# AD.net
KiCad netlist of a schematic drawn in Altium Designer
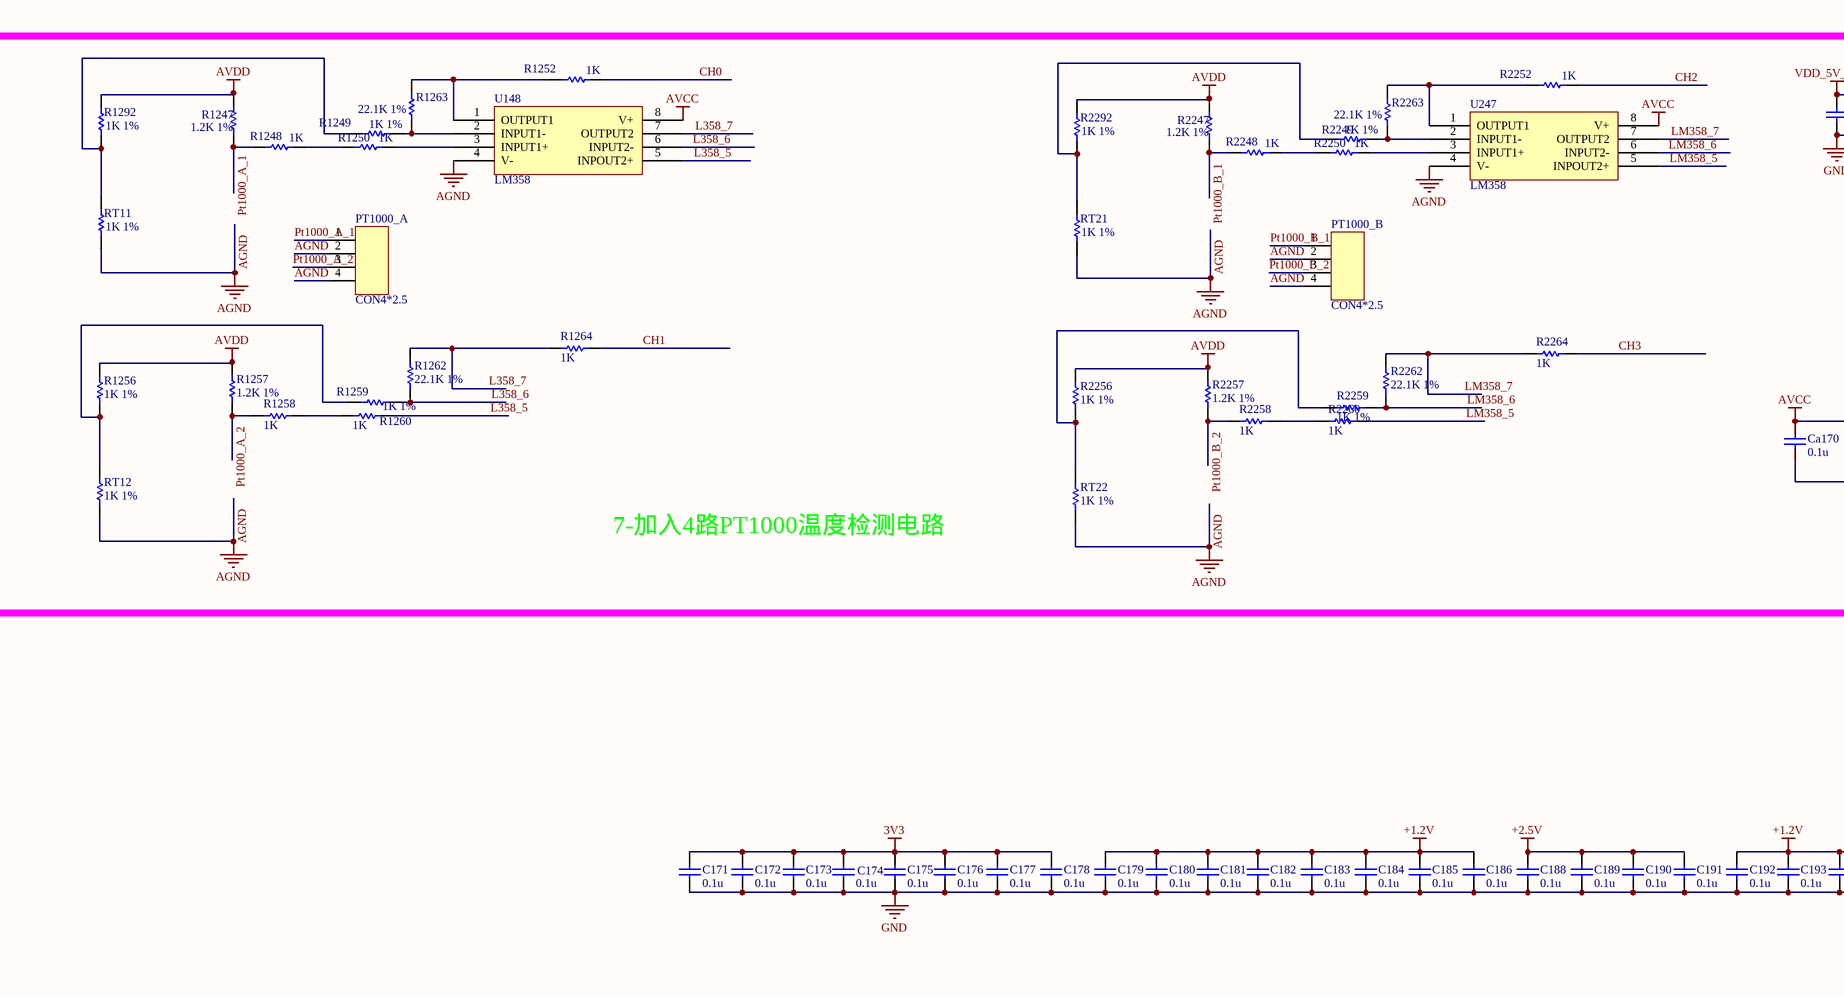
[diagram p0: AD.SchDoc, top left]
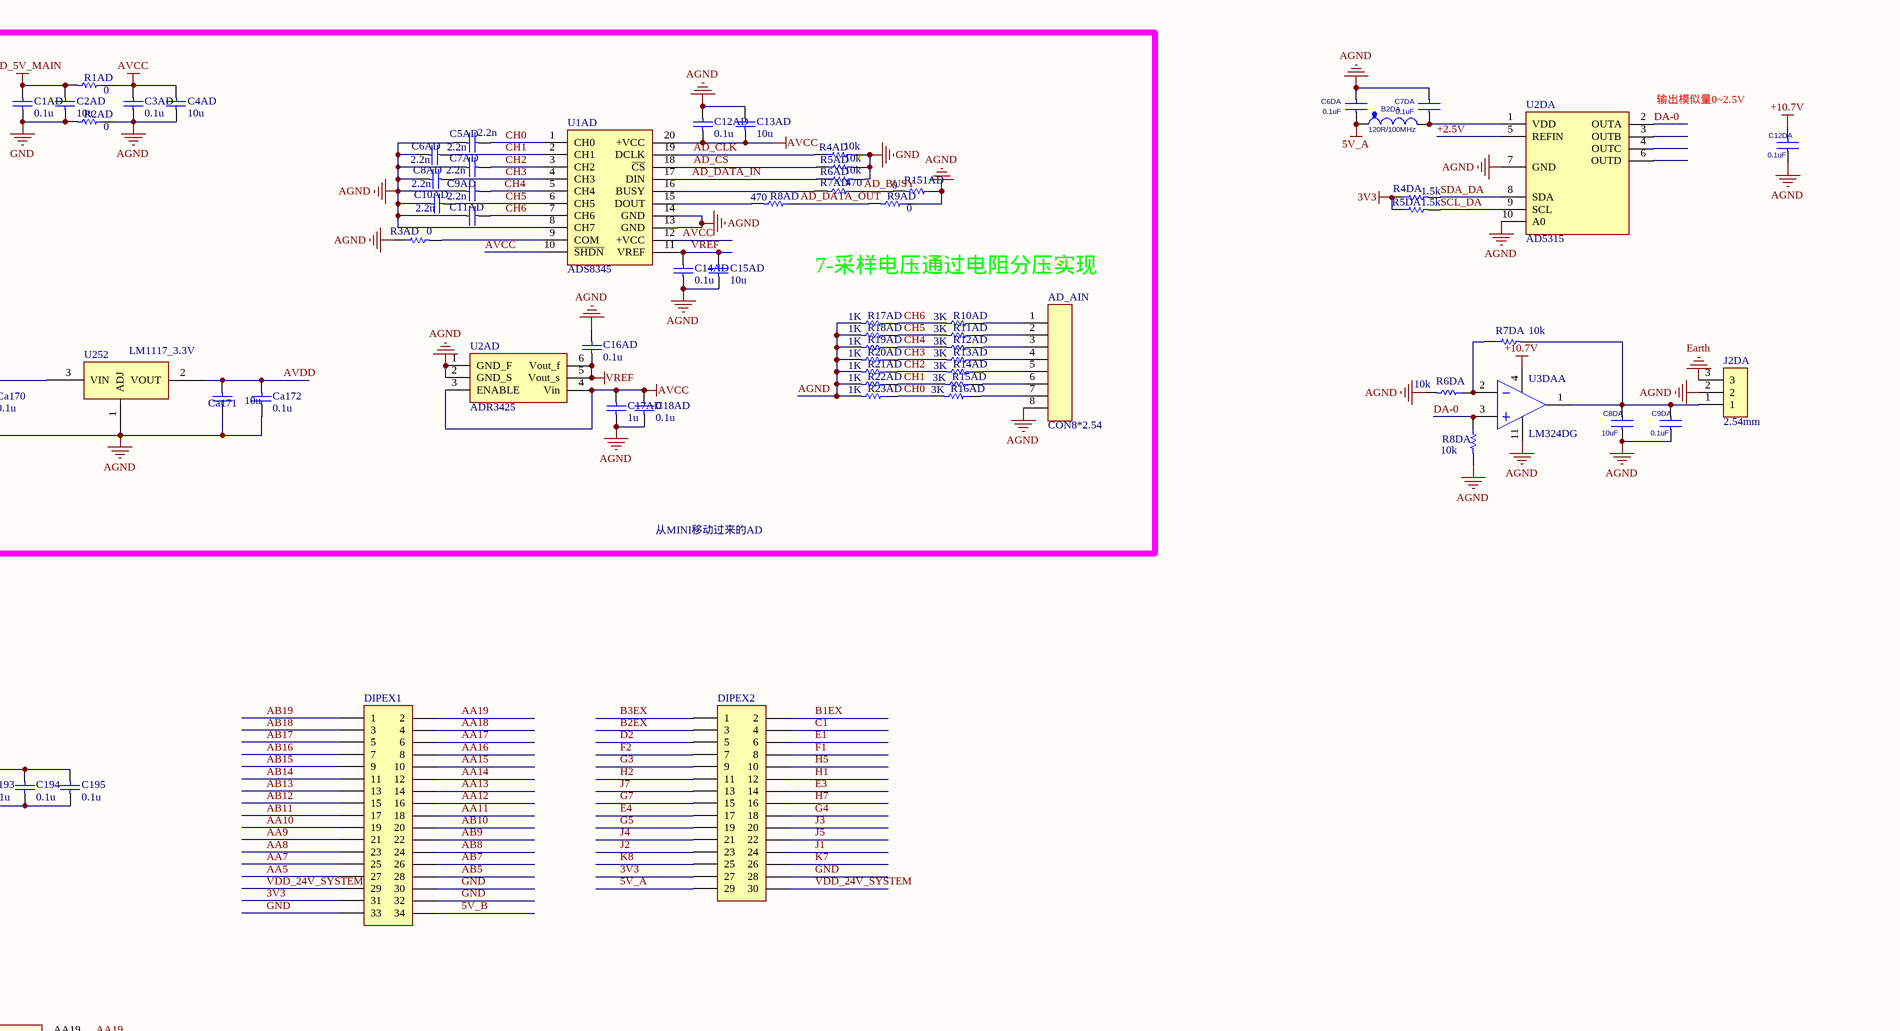
[diagram p1: AD.SchDoc, top right]
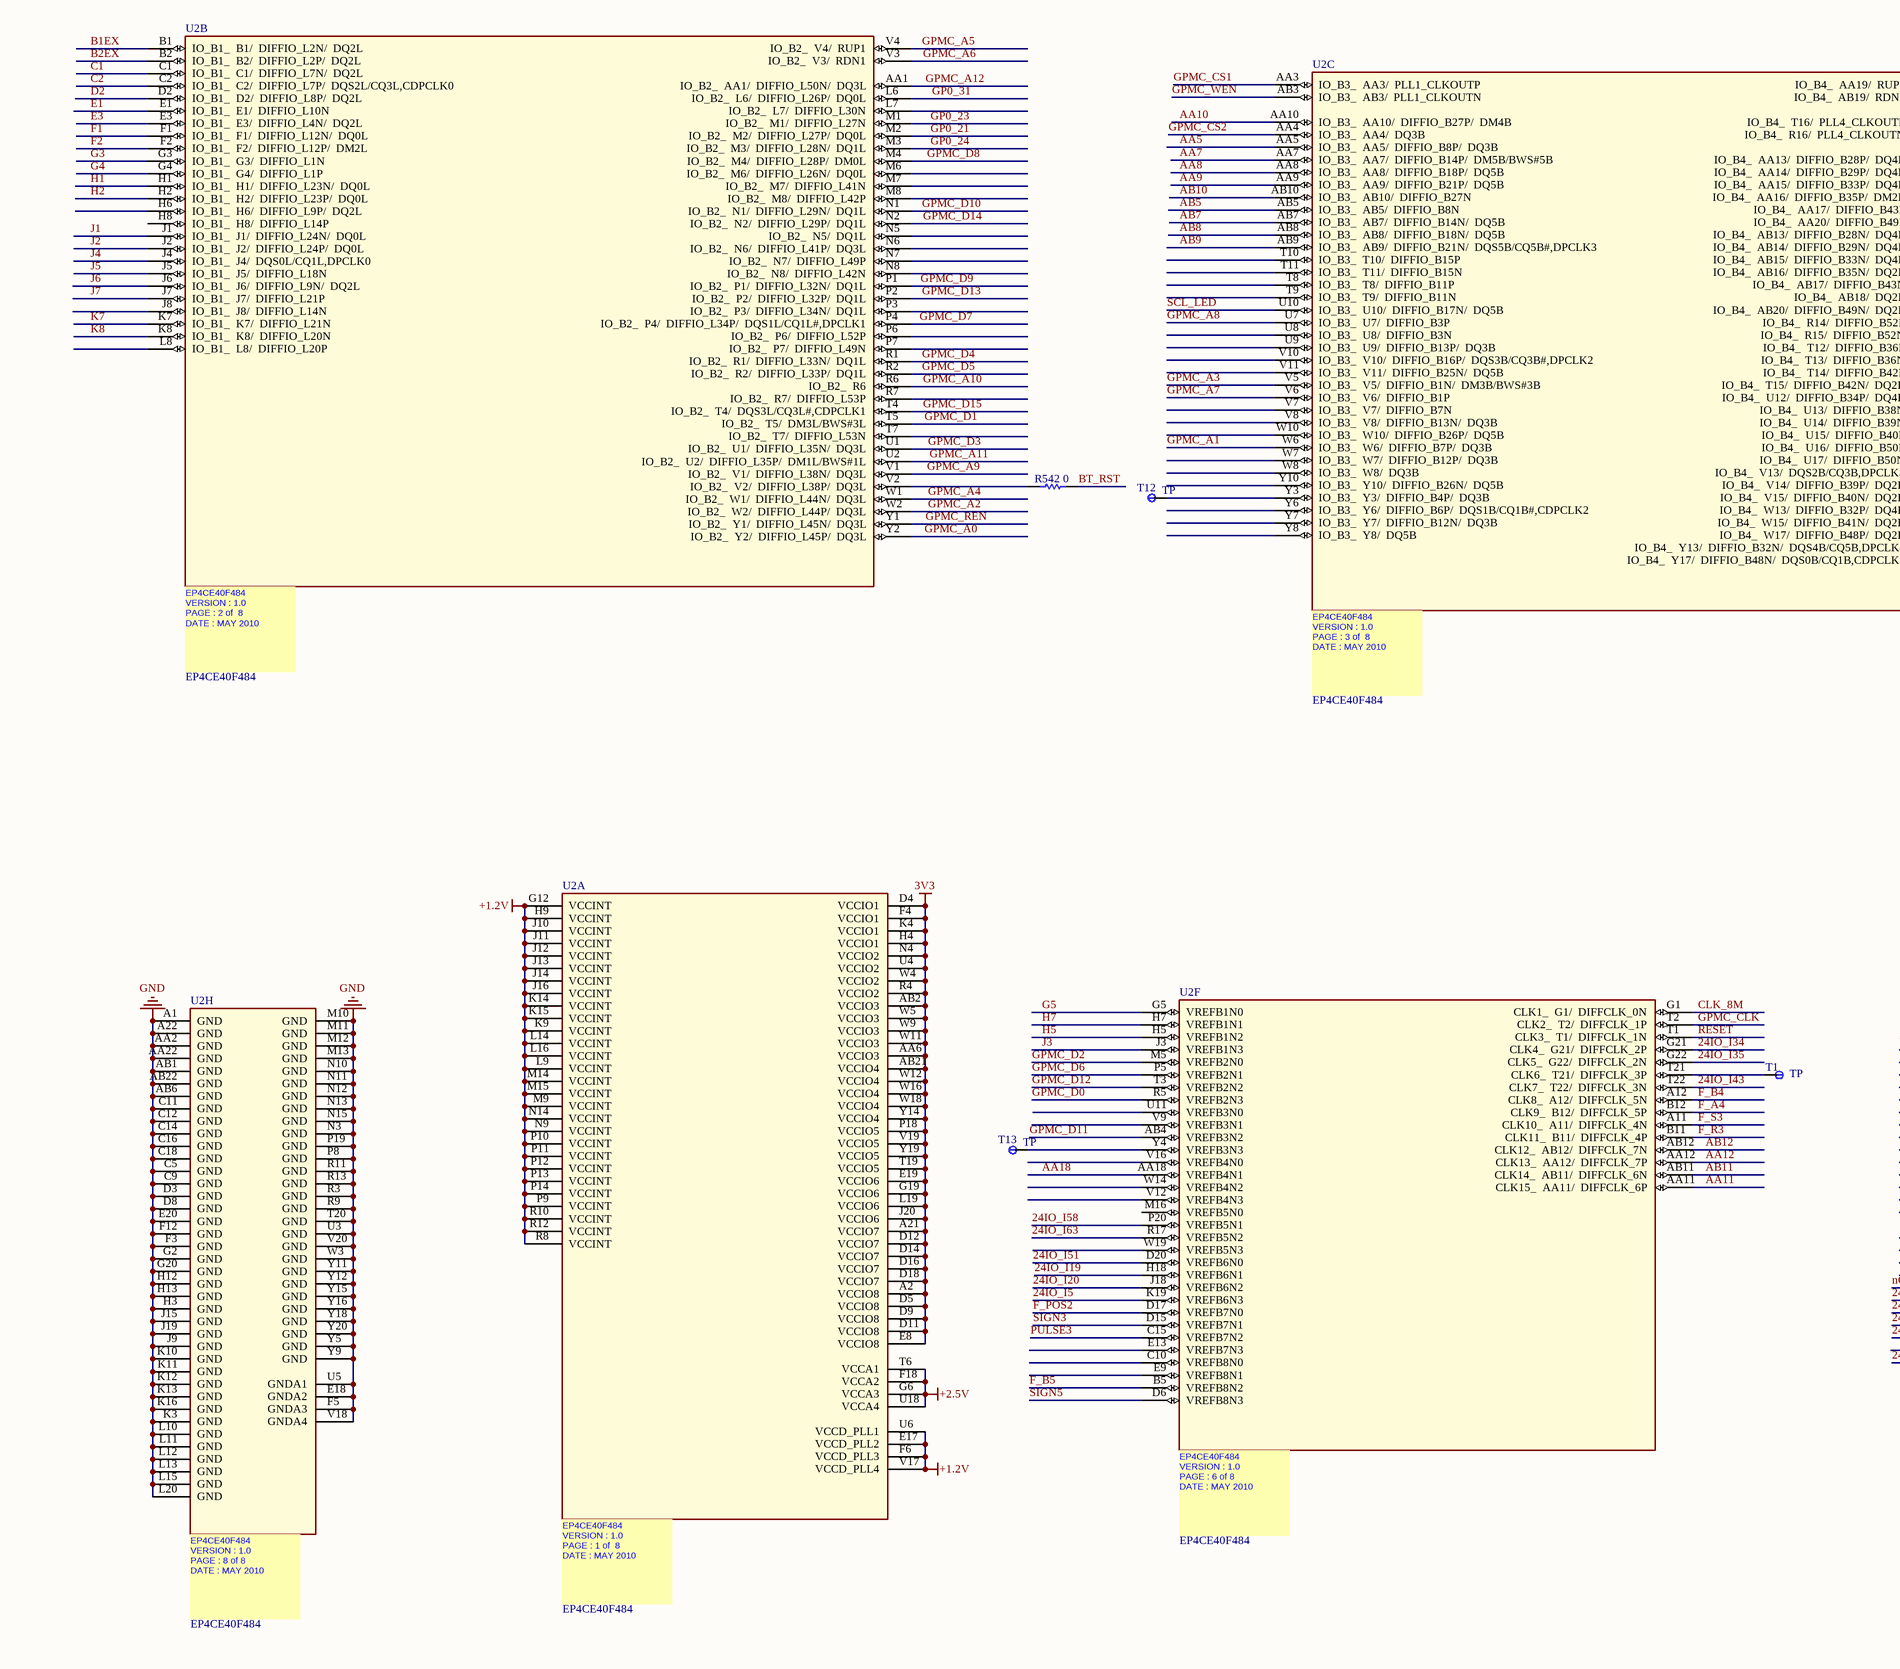
[diagram p2: AD.SchDoc, bottom left]
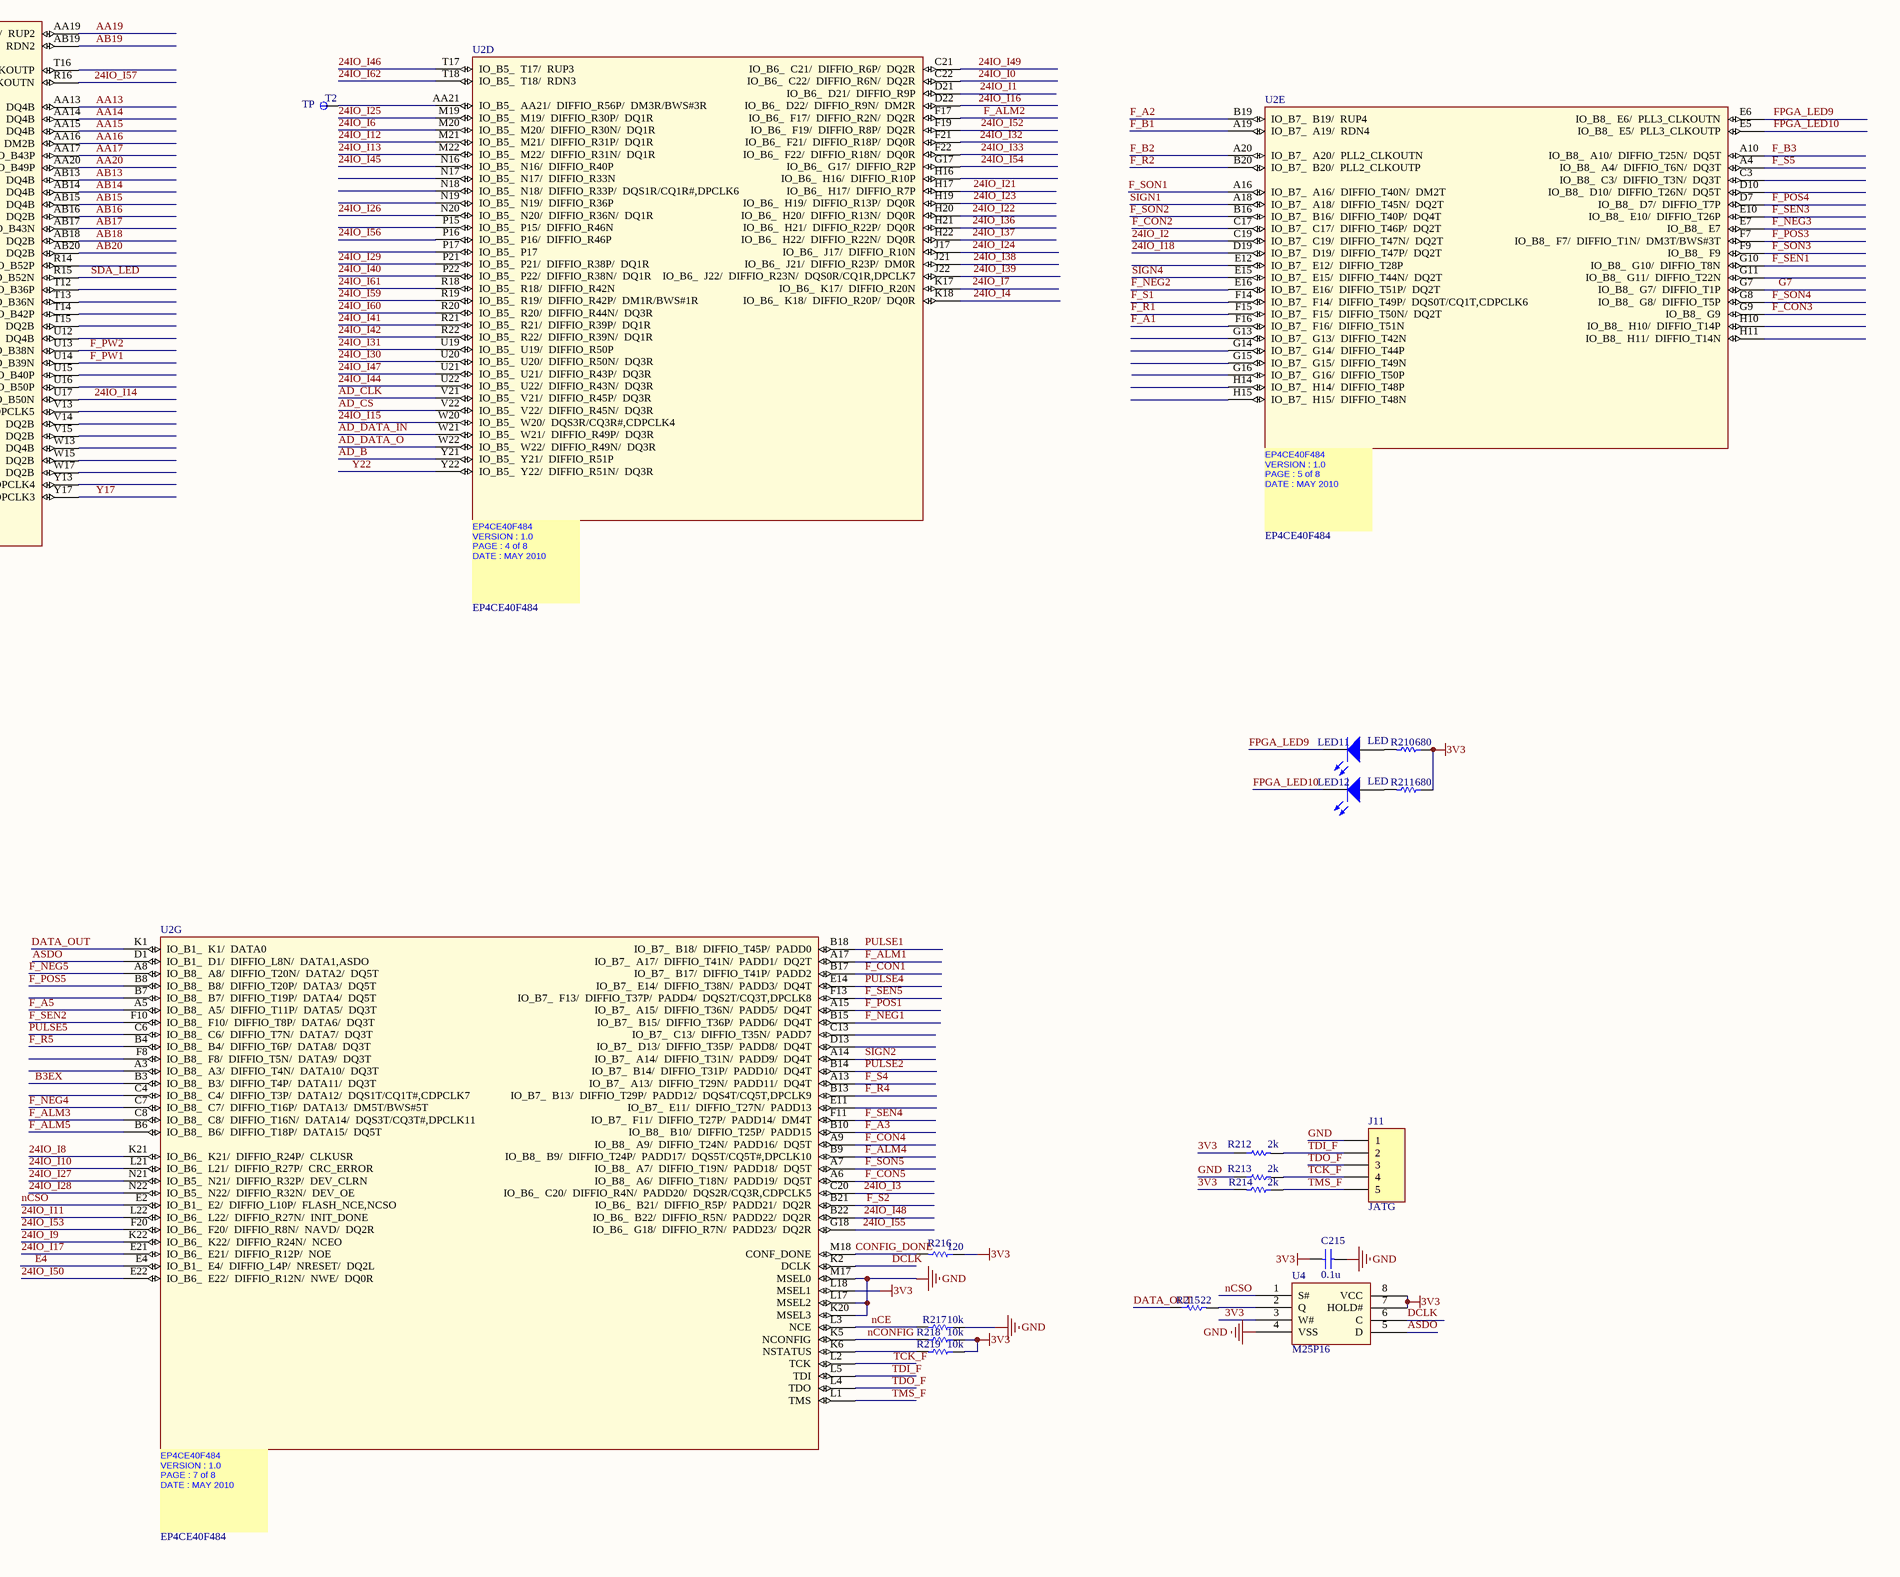
[diagram p3: AD.SchDoc, bottom right]

(export (version "E")
  (design (tool "Eeschema 10.0.6"))
  (components
    (comp (ref "AD_AIN")
      (value "CON8*2.54")
      (footprint "CON2.54mm*8")
      (libsource (lib "hcm") (part "CON8*2.54"))
    )
    (comp (ref "B2DA")
      (value "120R/100MHz")
      (footprint "R0603")
      (fields (field (name "MANUFACTURER PARTNUMBER") "MPZ1608S221A") (field (name "MANUFACTURER") "TDK"))
      (libsource (lib "*") (part "FERRITE BEAD"))
    )
    (comp (ref "C1AD") (value "0.1u") (footprint "0402") (libsource (lib "hcm") (part "0603C")))
    (comp (ref "C2AD") (value "10u") (footprint "C0805") (libsource (lib "hcm") (part "0603C")))
    (comp (ref "C3AD") (value "0.1u") (footprint "0402") (libsource (lib "hcm") (part "0603C")))
    (comp (ref "C4AD") (value "10u") (footprint "C0805") (libsource (lib "hcm") (part "0603C")))
    (comp (ref "C5AD") (value "2.2n") (footprint "C0603") (libsource (lib "hcm") (part "0603C")))
    (comp (ref "C6AD") (value "2.2n") (footprint "C0603") (libsource (lib "hcm") (part "0603C")))
    (comp (ref "C6DA")
      (value "0.1uF")
      (footprint "C0603")
      (description "CAP .10UF 50V CERAMIC X7R")
      (fields (field (name "MANUFACTURER") "Kemet"))
      (libsource (lib "*") (part "CAPACITOR NON-POL_Dup2"))
    )
    (comp (ref "C7AD") (value "2.2n") (footprint "C0603") (libsource (lib "hcm") (part "0603C")))
    (comp (ref "C7DA")
      (value "0.1uF")
      (footprint "C0603")
      (description "CAP .10UF 50V CERAMIC X7R")
      (fields (field (name "MANUFACTURER") "Kemet"))
      (libsource (lib "*") (part "CAPACITOR NON-POL_Dup2"))
    )
    (comp (ref "C8AD") (value "2.2n") (footprint "C0603") (libsource (lib "hcm") (part "0603C")))
    (comp (ref "C8DA")
      (value "10uF")
      (footprint "C0805")
      (description "CAP .10UF 50V CERAMIC X7R")
      (fields (field (name "MANUFACTURER") "Kemet"))
      (libsource (lib "*") (part "CAPACITOR NON-POL_Dup2"))
    )
    (comp (ref "C9AD") (value "2.2n") (footprint "C0603") (libsource (lib "hcm") (part "0603C")))
    (comp (ref "C9DA")
      (value "0.1uF")
      (footprint "C0603")
      (description "CAP .10UF 50V CERAMIC X7R")
      (fields (field (name "MANUFACTURER") "Kemet"))
      (libsource (lib "*") (part "CAPACITOR NON-POL_Dup2"))
    )
    (comp (ref "C10AD") (value "2.2n") (footprint "C0603") (libsource (lib "hcm") (part "0603C")))
    (comp (ref "C11AD") (value "2.2n") (footprint "C0603") (libsource (lib "hcm") (part "0603C")))
    (comp (ref "C12AD") (value "0.1u") (footprint "0402") (libsource (lib "hcm") (part "0603C")))
    (comp (ref "C12DA")
      (value "0.1uF")
      (footprint "C0603")
      (description "CAP .10UF 50V CERAMIC X7R")
      (fields (field (name "MANUFACTURER") "Kemet"))
      (libsource (lib "*") (part "CAPACITOR NON-POL_Dup2"))
    )
    (comp (ref "C13AD") (value "10u") (footprint "C0805") (libsource (lib "hcm") (part "0603C")))
    (comp (ref "C14AD") (value "0.1u") (footprint "0402") (libsource (lib "hcm") (part "0603C")))
    (comp (ref "C15AD") (value "10u") (footprint "C0805") (libsource (lib "hcm") (part "0603C")))
    (comp (ref "C16AD") (value "0.1u") (footprint "0402") (libsource (lib "hcm") (part "0603C")))
    (comp (ref "C17AD") (value "1u") (footprint "C0603") (libsource (lib "hcm") (part "0603C")))
    (comp (ref "C18AD") (value "0.1u") (footprint "0402") (libsource (lib "hcm") (part "0603C")))
    (comp (ref "C171") (value "0.1u") (footprint "C0402") (libsource (lib "hcm") (part "0603C")))
    (comp (ref "C172") (value "0.1u") (footprint "C0402") (libsource (lib "hcm") (part "0603C")))
    (comp (ref "C173") (value "0.1u") (footprint "C0402") (libsource (lib "hcm") (part "0603C")))
    (comp (ref "C174") (value "0.1u") (footprint "C0402") (libsource (lib "hcm") (part "0603C")))
    (comp (ref "C175") (value "0.1u") (footprint "C0402") (libsource (lib "hcm") (part "0603C")))
    (comp (ref "C176") (value "0.1u") (footprint "C0402") (libsource (lib "hcm") (part "0603C")))
    (comp (ref "C177") (value "0.1u") (footprint "C0402") (libsource (lib "hcm") (part "0603C")))
    (comp (ref "C178") (value "0.1u") (footprint "C0402") (libsource (lib "hcm") (part "0603C")))
    (comp (ref "C179") (value "0.1u") (footprint "C0402") (libsource (lib "hcm") (part "0603C")))
    (comp (ref "C180") (value "0.1u") (footprint "C0402") (libsource (lib "hcm") (part "0603C")))
    (comp (ref "C181") (value "0.1u") (footprint "C0402") (libsource (lib "hcm") (part "0603C")))
    (comp (ref "C182") (value "0.1u") (footprint "C0402") (libsource (lib "hcm") (part "0603C")))
    (comp (ref "C183") (value "0.1u") (footprint "C0402") (libsource (lib "hcm") (part "0603C")))
    (comp (ref "C184") (value "0.1u") (footprint "C0402") (libsource (lib "hcm") (part "0603C")))
    (comp (ref "C185") (value "0.1u") (footprint "C0402") (libsource (lib "hcm") (part "0603C")))
    (comp (ref "C186") (value "0.1u") (footprint "C0402") (libsource (lib "hcm") (part "0603C")))
    (comp (ref "C188") (value "0.1u") (footprint "C0402") (libsource (lib "hcm") (part "0603C")))
    (comp (ref "C189") (value "0.1u") (footprint "C0402") (libsource (lib "hcm") (part "0603C")))
    (comp (ref "C190") (value "0.1u") (footprint "C0402") (libsource (lib "hcm") (part "0603C")))
    (comp (ref "C191") (value "0.1u") (footprint "C0402") (libsource (lib "hcm") (part "0603C")))
    (comp (ref "C192") (value "0.1u") (footprint "C0402") (libsource (lib "hcm") (part "0603C")))
    (comp (ref "C193") (value "0.1u") (footprint "C0402") (libsource (lib "hcm") (part "0603C")))
    (comp (ref "C194") (value "0.1u") (footprint "C0402") (libsource (lib "hcm") (part "0603C")))
    (comp (ref "C195") (value "0.1u") (footprint "C0402") (libsource (lib "hcm") (part "0603C")))
    (comp (ref "C215") (value "0.1u") (footprint "C0402") (libsource (lib "Schlib1") (part "CAP")))
    (comp (ref "Ca170") (value "0.1u") (footprint "C0603") (libsource (lib "hcm") (part "0603C")))
    (comp (ref "Ca171") (value "10u") (footprint "C0805") (libsource (lib "hcm") (part "0603C")))
    (comp (ref "Ca172") (value "0.1u") (footprint "C0603") (libsource (lib "hcm") (part "0603C")))
    (comp (ref "DIPEX1")
      (value "~")
      (footprint "HDR2X17")
      (description "Header, 17-Pin, Dual row")
      (fields (field (name "PUBLISHER") "Altium Limited"))
      (libsource (lib "Miscellaneous Connectors") (part "Header 17X2"))
    )
    (comp (ref "DIPEX2")
      (value "~")
      (footprint "HDR2X15")
      (description "Header, 15-Pin, Dual row")
      (fields (field (name "PUBLISHER") "Altium Limited"))
      (libsource (lib "Miscellaneous Connectors") (part "Header 15X2"))
    )
    (comp (ref "J2DA") (value "2.54mm") (footprint "CON2.54MM*3") (libsource (lib "hcm") (part "CON3")))
    (comp (ref "J11") (value "JATG") (footprint "MHDR1X5") (libsource (lib "Schlib1") (part "HEAD5_1.27")))
    (comp (ref "LED11") (value "LED") (footprint "LED0603") (libsource (lib "Schlib1") (part "LED")))
    (comp (ref "LED12") (value "LED") (footprint "LED0603") (libsource (lib "Schlib1") (part "LED")))
    (comp (ref "PT1000_A")
      (value "CON4*2.5")
      (footprint "CON2.54MM*4")
      (libsource (lib "hcm") (part "CON4*2.5"))
    )
    (comp (ref "PT1000_B")
      (value "CON4*2.5")
      (footprint "CON2.54MM*4")
      (libsource (lib "hcm") (part "CON4*2.5"))
    )
    (comp (ref "R1AD") (value "0") (footprint "C0603") (libsource (lib "Schlib1") (part "RES")))
    (comp (ref "R2AD") (value "0") (footprint "C0603") (libsource (lib "Schlib1") (part "RES")))
    (comp (ref "R3AD") (value "0") (footprint "0402") (libsource (lib "Schlib1") (part "RES")))
    (comp (ref "R4AD") (value "10k") (footprint "0402") (libsource (lib "Schlib1") (part "RES")))
    (comp (ref "R4DA") (value "1.5k") (footprint "R0603") (libsource (lib "Schlib1") (part "RES")))
    (comp (ref "R5AD") (value "10k") (footprint "0402") (libsource (lib "Schlib1") (part "RES")))
    (comp (ref "R5DA") (value "1.5k") (footprint "R0603") (libsource (lib "Schlib1") (part "RES")))
    (comp (ref "R6AD") (value "10k") (footprint "0402") (libsource (lib "Schlib1") (part "RES")))
    (comp (ref "R6DA") (value "10k") (footprint "R0603") (libsource (lib "Schlib1") (part "RES")))
    (comp (ref "R7AD") (value "470") (footprint "0402") (libsource (lib "Schlib1") (part "RES")))
    (comp (ref "R7DA") (value "10k") (footprint "R0603") (libsource (lib "Schlib1") (part "RES")))
    (comp (ref "R8AD") (value "470") (footprint "0402") (libsource (lib "Schlib1") (part "RES")))
    (comp (ref "R8DA") (value "10k") (footprint "R0603") (libsource (lib "Schlib1") (part "RES")))
    (comp (ref "R9AD") (value "0") (footprint "R0603") (libsource (lib "Schlib1") (part "RES")))
    (comp (ref "R10AD") (value "3K") (footprint "0402") (libsource (lib "Schlib1") (part "RES")))
    (comp (ref "R11AD") (value "3K") (footprint "0402") (libsource (lib "Schlib1") (part "RES")))
    (comp (ref "R12AD") (value "3K") (footprint "0402") (libsource (lib "Schlib1") (part "RES")))
    (comp (ref "R13AD") (value "3K") (footprint "0402") (libsource (lib "Schlib1") (part "RES")))
    (comp (ref "R14AD") (value "3K") (footprint "0402") (libsource (lib "Schlib1") (part "RES")))
    (comp (ref "R15AD") (value "3K") (footprint "0402") (libsource (lib "Schlib1") (part "RES")))
    (comp (ref "R16AD") (value "3K") (footprint "0402") (libsource (lib "Schlib1") (part "RES")))
    (comp (ref "R17AD") (value "1K") (footprint "0402") (libsource (lib "Schlib1") (part "RES")))
    (comp (ref "R18AD") (value "1K") (footprint "0402") (libsource (lib "Schlib1") (part "RES")))
    (comp (ref "R19AD") (value "1K") (footprint "0402") (libsource (lib "Schlib1") (part "RES")))
    (comp (ref "R20AD") (value "1K") (footprint "0402") (libsource (lib "Schlib1") (part "RES")))
    (comp (ref "R21AD") (value "1K") (footprint "0402") (libsource (lib "Schlib1") (part "RES")))
    (comp (ref "R22AD") (value "1K") (footprint "0402") (libsource (lib "Schlib1") (part "RES")))
    (comp (ref "R23AD") (value "1K") (footprint "0402") (libsource (lib "Schlib1") (part "RES")))
    (comp (ref "R151AD") (value "0") (footprint "R0603") (libsource (lib "Schlib1") (part "RES")))
    (comp (ref "R210") (value "680") (footprint "R0603") (libsource (lib "Schlib1") (part "RES")))
    (comp (ref "R211") (value "680") (footprint "R0603") (libsource (lib "Schlib1") (part "RES")))
    (comp (ref "R212") (value "2k") (footprint "R0603") (libsource (lib "Schlib1") (part "RES")))
    (comp (ref "R213") (value "2k") (footprint "R0603") (libsource (lib "Schlib1") (part "RES")))
    (comp (ref "R214") (value "2k") (footprint "R0603") (libsource (lib "Schlib1") (part "RES")))
    (comp (ref "R215") (value "22") (footprint "R0603") (libsource (lib "Schlib1") (part "RES")))
    (comp (ref "R216") (value "120") (footprint "R0603") (libsource (lib "Schlib1") (part "RES")))
    (comp (ref "R217") (value "10k") (footprint "R0603") (libsource (lib "Schlib1") (part "RES")))
    (comp (ref "R218") (value "10k") (footprint "R0603") (libsource (lib "Schlib1") (part "RES")))
    (comp (ref "R219") (value "10k") (footprint "R0603") (libsource (lib "Schlib1") (part "RES")))
    (comp (ref "R542") (value "0") (footprint "R0603") (libsource (lib "Schlib1") (part "RES")))
    (comp (ref "R1247") (value "1.2K 1%") (footprint "R0603") (libsource (lib "Schlib1") (part "RES")))
    (comp (ref "R1248") (value "1K") (footprint "R0603") (libsource (lib "Schlib1") (part "RES")))
    (comp (ref "R1249") (value "1K 1%") (footprint "R0603") (libsource (lib "Schlib1") (part "RES")))
    (comp (ref "R1250") (value "1K") (footprint "R0603") (libsource (lib "Schlib1") (part "RES")))
    (comp (ref "R1252") (value "1K") (footprint "R0603") (libsource (lib "Schlib1") (part "RES")))
    (comp (ref "R1256") (value "1K 1%") (footprint "R0603") (libsource (lib "Schlib1") (part "RES")))
    (comp (ref "R1257") (value "1.2K 1%") (footprint "R0603") (libsource (lib "Schlib1") (part "RES")))
    (comp (ref "R1258") (value "1K") (footprint "R0603") (libsource (lib "Schlib1") (part "RES")))
    (comp (ref "R1259") (value "1K 1%") (footprint "R0603") (libsource (lib "Schlib1") (part "RES")))
    (comp (ref "R1260") (value "1K") (footprint "R0603") (libsource (lib "Schlib1") (part "RES")))
    (comp (ref "R1262") (value "22.1K 1%") (footprint "R0603") (libsource (lib "Schlib1") (part "RES")))
    (comp (ref "R1263") (value "22.1K 1%") (footprint "R0603") (libsource (lib "Schlib1") (part "RES")))
    (comp (ref "R1264") (value "1K") (footprint "R0603") (libsource (lib "Schlib1") (part "RES")))
    (comp (ref "R1292") (value "1K 1%") (footprint "R0603") (libsource (lib "Schlib1") (part "RES")))
    (comp (ref "R2247") (value "1.2K 1%") (footprint "R0603") (libsource (lib "Schlib1") (part "RES")))
    (comp (ref "R2248") (value "1K") (footprint "R0603") (libsource (lib "Schlib1") (part "RES")))
    (comp (ref "R2249") (value "1K 1%") (footprint "R0603") (libsource (lib "Schlib1") (part "RES")))
    (comp (ref "R2250") (value "1K") (footprint "R0603") (libsource (lib "Schlib1") (part "RES")))
    (comp (ref "R2252") (value "1K") (footprint "R0603") (libsource (lib "Schlib1") (part "RES")))
    (comp (ref "R2256") (value "1K 1%") (footprint "R0603") (libsource (lib "Schlib1") (part "RES")))
    (comp (ref "R2257") (value "1.2K 1%") (footprint "R0603") (libsource (lib "Schlib1") (part "RES")))
    (comp (ref "R2258") (value "1K") (footprint "R0603") (libsource (lib "Schlib1") (part "RES")))
    (comp (ref "R2259") (value "1K 1%") (footprint "R0603") (libsource (lib "Schlib1") (part "RES")))
    (comp (ref "R2260") (value "1K") (footprint "R0603") (libsource (lib "Schlib1") (part "RES")))
    (comp (ref "R2262") (value "22.1K 1%") (footprint "R0603") (libsource (lib "Schlib1") (part "RES")))
    (comp (ref "R2263") (value "22.1K 1%") (footprint "R0603") (libsource (lib "Schlib1") (part "RES")))
    (comp (ref "R2264") (value "1K") (footprint "R0603") (libsource (lib "Schlib1") (part "RES")))
    (comp (ref "R2292") (value "1K 1%") (footprint "R0603") (libsource (lib "Schlib1") (part "RES")))
    (comp (ref "RT11") (value "1K 1%") (footprint "R0603") (libsource (lib "Schlib1") (part "RES")))
    (comp (ref "RT12") (value "1K 1%") (footprint "R0603") (libsource (lib "Schlib1") (part "RES")))
    (comp (ref "RT21") (value "1K 1%") (footprint "R0603") (libsource (lib "Schlib1") (part "RES")))
    (comp (ref "RT22") (value "1K 1%") (footprint "R0603") (libsource (lib "Schlib1") (part "RES")))
    (comp (ref "T1") (value "TP") (footprint "TP") (libsource (lib "hcm") (part "TP")))
    (comp (ref "T2") (value "TP") (footprint "TP") (libsource (lib "hcm") (part "TP")))
    (comp (ref "T12") (value "TP") (footprint "TP") (libsource (lib "hcm") (part "TP")))
    (comp (ref "T13") (value "TP") (footprint "TP") (libsource (lib "hcm") (part "TP")))
    (comp (ref "U1AD") (value "ADS8345") (footprint "TSSOP20") (libsource (lib "hcm") (part "ADS8345")))
    (comp (ref "U2")
      (value "EP4CE40F484")
      (footprint "F484")
      (libsource (lib "EP4CE40_Library") (part "EP4CE40F484"))
    )
    (comp (ref "U2AD") (value "ADR3425") (footprint "SOT-23-6") (libsource (lib "hcm") (part "ADR3425")))
    (comp (ref "U2DA") (value "AD5315") (footprint "MSOP") (libsource (lib "hcm") (part "AD5315")))
    (comp (ref "U3DA")
      (value "LM324DG")
      (footprint "SO-14")
      (description "运算放大器")
      (libsource (lib "*") (part "OPAMP"))
    )
    (comp (ref "U4") (value "M25P16") (footprint "SO-G8") (libsource (lib "Schlib1") (part "MP25P16")))
    (comp (ref "U148") (value "LM358") (footprint "SO-G8") (libsource (lib "hcm") (part "4580")))
    (comp (ref "U247") (value "LM358") (footprint "SO-G8") (libsource (lib "hcm") (part "4580")))
    (comp (ref "U252") (value "LM1117_3.3V") (footprint "SOT223") (libsource (lib "Schlib1") (part "LM1117")))
  )
  (nets
    (net (code "1") (name "+1.2V") (class "Default")
      (node (ref "C179") (pin "2") (pinfunction "2_2") (pintype "passive"))
      (node (ref "C180") (pin "2") (pinfunction "2_2") (pintype "passive"))
      (node (ref "C181") (pin "2") (pinfunction "2_2") (pintype "passive"))
      (node (ref "C182") (pin "2") (pinfunction "2_2") (pintype "passive"))
      (node (ref "C183") (pin "2") (pinfunction "2_2") (pintype "passive"))
      (node (ref "C184") (pin "2") (pinfunction "2_2") (pintype "passive"))
      (node (ref "C185") (pin "2") (pinfunction "2_2") (pintype "passive"))
      (node (ref "C186") (pin "2") (pinfunction "2_2") (pintype "passive"))
      (node (ref "C192") (pin "2") (pinfunction "2_2") (pintype "passive"))
      (node (ref "C193") (pin "2") (pinfunction "2_2") (pintype "passive"))
      (node (ref "C194") (pin "2") (pinfunction "2_2") (pintype "passive"))
      (node (ref "C195") (pin "2") (pinfunction "2_2") (pintype "passive"))
      (node (ref "U2") (pin "E17") (pinfunction "VCCD_PLL2_E17") (pintype "power_in"))
      (node (ref "U2") (pin "F6") (pinfunction "VCCD_PLL3_F6") (pintype "power_in"))
      (node (ref "U2") (pin "G12") (pinfunction "VCCINT_G12") (pintype "power_in"))
      (node (ref "U2") (pin "H9") (pinfunction "VCCINT_H9") (pintype "power_in"))
      (node (ref "U2") (pin "J10") (pinfunction "VCCINT_J10") (pintype "power_in"))
      (node (ref "U2") (pin "J11") (pinfunction "VCCINT_J11") (pintype "power_in"))
      (node (ref "U2") (pin "J12") (pinfunction "VCCINT_J12") (pintype "power_in"))
      (node (ref "U2") (pin "J13") (pinfunction "VCCINT_J13") (pintype "power_in"))
      (node (ref "U2") (pin "J14") (pinfunction "VCCINT_J14") (pintype "power_in"))
      (node (ref "U2") (pin "J16") (pinfunction "VCCINT_J16") (pintype "power_in"))
      (node (ref "U2") (pin "K14") (pinfunction "VCCINT_K14") (pintype "power_in"))
      (node (ref "U2") (pin "K15") (pinfunction "VCCINT_K15") (pintype "power_in"))
      (node (ref "U2") (pin "K9") (pinfunction "VCCINT_K9") (pintype "power_in"))
      (node (ref "U2") (pin "L14") (pinfunction "VCCINT_L14") (pintype "power_in"))
      (node (ref "U2") (pin "L16") (pinfunction "VCCINT_L16") (pintype "power_in"))
      (node (ref "U2") (pin "L9") (pinfunction "VCCINT_L9") (pintype "power_in"))
      (node (ref "U2") (pin "M14") (pinfunction "VCCINT_M14") (pintype "power_in"))
      (node (ref "U2") (pin "M15") (pinfunction "VCCINT_M15") (pintype "power_in"))
      (node (ref "U2") (pin "M9") (pinfunction "VCCINT_M9") (pintype "power_in"))
      (node (ref "U2") (pin "N14") (pinfunction "VCCINT_N14") (pintype "power_in"))
      (node (ref "U2") (pin "N9") (pinfunction "VCCINT_N9") (pintype "power_in"))
      (node (ref "U2") (pin "P10") (pinfunction "VCCINT_P10") (pintype "power_in"))
      (node (ref "U2") (pin "P11") (pinfunction "VCCINT_P11") (pintype "power_in"))
      (node (ref "U2") (pin "P12") (pinfunction "VCCINT_P12") (pintype "power_in"))
      (node (ref "U2") (pin "P13") (pinfunction "VCCINT_P13") (pintype "power_in"))
      (node (ref "U2") (pin "P14") (pinfunction "VCCINT_P14") (pintype "power_in"))
      (node (ref "U2") (pin "P9") (pinfunction "VCCINT_P9") (pintype "power_in"))
      (node (ref "U2") (pin "R10") (pinfunction "VCCINT_R10") (pintype "power_in"))
      (node (ref "U2") (pin "R12") (pinfunction "VCCINT_R12") (pintype "power_in"))
      (node (ref "U2") (pin "R8") (pinfunction "VCCINT_R8") (pintype "power_in"))
      (node (ref "U2") (pin "U6") (pinfunction "VCCD_PLL1_U6") (pintype "power_in"))
      (node (ref "U2") (pin "V17") (pinfunction "VCCD_PLL4_V17") (pintype "power_in"))
    )
    (net (code "2") (name "+2.5V") (class "Default")
      (node (ref "C188") (pin "2") (pinfunction "2_2") (pintype "passive"))
      (node (ref "C189") (pin "2") (pinfunction "2_2") (pintype "passive"))
      (node (ref "C190") (pin "2") (pinfunction "2_2") (pintype "passive"))
      (node (ref "C191") (pin "2") (pinfunction "2_2") (pintype "passive"))
      (node (ref "U2") (pin "F18") (pinfunction "VCCA2_F18") (pintype "power_in"))
      (node (ref "U2") (pin "G6") (pinfunction "VCCA3_G6") (pintype "power_in"))
      (node (ref "U2") (pin "T6") (pinfunction "VCCA1_T6") (pintype "power_in"))
      (node (ref "U2") (pin "U18") (pinfunction "VCCA4_U18") (pintype "power_in"))
      (node (ref "U2DA") (pin "5") (pinfunction "REFIN_5") (pintype "passive"))
    )
    (net (code "3") (name "+10.7V") (class "Default")
      (node (ref "C12DA") (pin "2") (pinfunction "2_2") (pintype "passive"))
      (node (ref "U3DA") (pin "4") (pinfunction "VDD_4") (pintype "power_in"))
    )
    (net (code "4") (name "/5V_B") (class "Default")
      (node (ref "DIPEX1") (pin "34") (pinfunction "34_34") (pintype "passive"))
    )
    (net (code "5") (name "/24IO_I0") (class "Default")
      (node (ref "U2") (pin "C22") (pinfunction "IO_B6___C22/__DIFFIO_R6N/__DQ2R_C22") (pintype "bidirectional"))
    )
    (net (code "6") (name "/24IO_I1") (class "Default")
      (node (ref "U2") (pin "D21") (pinfunction "IO_B6___D21/__DIFFIO_R9P_D21") (pintype "bidirectional"))
    )
    (net (code "7") (name "/24IO_I2") (class "Default")
      (node (ref "U2") (pin "C19") (pinfunction "IO_B7___C19/__DIFFIO_T47N/__DQ2T_C19") (pintype "bidirectional"))
    )
    (net (code "8") (name "/24IO_I3") (class "Default")
      (node (ref "U2") (pin "C20") (pinfunction "IO_B6___C20/__DIFFIO_R4N/__PADD20/__DQS2R/CQ3R,CDPCLK5_C20") (pintype "bidirectional"))
    )
    (net (code "9") (name "/24IO_I4") (class "Default")
      (node (ref "U2") (pin "K18") (pinfunction "IO_B6___K18/__DIFFIO_R20P/__DQ0R_K18") (pintype "bidirectional"))
    )
    (net (code "10") (name "/24IO_I5") (class "Default")
      (node (ref "U2") (pin "K19") (pinfunction "VREFB6N3_K19") (pintype "bidirectional"))
    )
    (net (code "11") (name "/24IO_I6") (class "Default")
      (node (ref "U2") (pin "M20") (pinfunction "IO_B5___M20/__DIFFIO_R30N/__DQ1R_M20") (pintype "bidirectional"))
    )
    (net (code "12") (name "/24IO_I7") (class "Default")
      (node (ref "U2") (pin "K17") (pinfunction "IO_B6___K17/__DIFFIO_R20N_K17") (pintype "bidirectional"))
    )
    (net (code "13") (name "/24IO_I8") (class "Default")
      (node (ref "U2") (pin "K21") (pinfunction "IO_B6___K21/__DIFFIO_R24P/__CLKUSR_K21") (pintype "bidirectional"))
    )
    (net (code "14") (name "/24IO_I9") (class "Default")
      (node (ref "U2") (pin "K22") (pinfunction "IO_B6___K22/__DIFFIO_R24N/__NCEO_K22") (pintype "bidirectional"))
    )
    (net (code "15") (name "/24IO_I10") (class "Default")
      (node (ref "U2") (pin "L21") (pinfunction "IO_B6___L21/__DIFFIO_R27P/__CRC_ERROR_L21") (pintype "bidirectional"))
    )
    (net (code "16") (name "/24IO_I11") (class "Default")
      (node (ref "U2") (pin "L22") (pinfunction "IO_B6___L22/__DIFFIO_R27N/__INIT_DONE_L22") (pintype "bidirectional"))
    )
    (net (code "17") (name "/24IO_I12") (class "Default")
      (node (ref "U2") (pin "M21") (pinfunction "IO_B5___M21/__DIFFIO_R31P/__DQ1R_M21") (pintype "bidirectional"))
    )
    (net (code "18") (name "/24IO_I13") (class "Default")
      (node (ref "U2") (pin "M22") (pinfunction "IO_B5___M22/__DIFFIO_R31N/__DQ1R_M22") (pintype "bidirectional"))
    )
    (net (code "19") (name "/24IO_I14") (class "Default")
      (node (ref "U2") (pin "U17") (pinfunction "IO_B4___U17/__DIFFIO_B50N_U17") (pintype "bidirectional"))
    )
    (net (code "20") (name "/24IO_I15") (class "Default")
      (node (ref "U2") (pin "W20") (pinfunction "IO_B5___W20/__DQS3R/CQ3R#,CDPCLK4_W20") (pintype "bidirectional"))
    )
    (net (code "21") (name "/24IO_I16") (class "Default")
      (node (ref "U2") (pin "D22") (pinfunction "IO_B6___D22/__DIFFIO_R9N/__DM2R_D22") (pintype "bidirectional"))
    )
    (net (code "22") (name "/24IO_I17") (class "Default")
      (node (ref "U2") (pin "E21") (pinfunction "IO_B6___E21/__DIFFIO_R12P/__NOE_E21") (pintype "bidirectional"))
    )
    (net (code "23") (name "/24IO_I18") (class "Default")
      (node (ref "U2") (pin "D19") (pinfunction "IO_B7___D19/__DIFFIO_T47P/__DQ2T_D19") (pintype "bidirectional"))
    )
    (net (code "24") (name "/24IO_I19") (class "Default")
      (node (ref "U2") (pin "H18") (pinfunction "VREFB6N1_H18") (pintype "bidirectional"))
    )
    (net (code "25") (name "/24IO_I20") (class "Default")
      (node (ref "U2") (pin "J18") (pinfunction "VREFB6N2_J18") (pintype "bidirectional"))
    )
    (net (code "26") (name "/24IO_I21") (class "Default")
      (node (ref "U2") (pin "H17") (pinfunction "IO_B6___H17/__DIFFIO_R7P_H17") (pintype "bidirectional"))
    )
    (net (code "27") (name "/24IO_I22") (class "Default")
      (node (ref "U2") (pin "H20") (pinfunction "IO_B6___H20/__DIFFIO_R13N/__DQ0R_H20") (pintype "bidirectional"))
    )
    (net (code "28") (name "/24IO_I23") (class "Default")
      (node (ref "U2") (pin "H19") (pinfunction "IO_B6___H19/__DIFFIO_R13P/__DQ0R_H19") (pintype "bidirectional"))
    )
    (net (code "29") (name "/24IO_I24") (class "Default")
      (node (ref "U2") (pin "J17") (pinfunction "IO_B6___J17/__DIFFIO_R10N_J17") (pintype "bidirectional"))
    )
    (net (code "30") (name "/24IO_I25") (class "Default")
      (node (ref "U2") (pin "M19") (pinfunction "IO_B5___M19/__DIFFIO_R30P/__DQ1R_M19") (pintype "bidirectional"))
    )
    (net (code "31") (name "/24IO_I26") (class "Default")
      (node (ref "U2") (pin "N20") (pinfunction "IO_B5___N20/__DIFFIO_R36N/__DQ1R_N20") (pintype "bidirectional"))
    )
    (net (code "32") (name "/24IO_I27") (class "Default")
      (node (ref "U2") (pin "N21") (pinfunction "IO_B5___N21/__DIFFIO_R32P/__DEV_CLRN_N21") (pintype "bidirectional"))
    )
    (net (code "33") (name "/24IO_I28") (class "Default")
      (node (ref "U2") (pin "N22") (pinfunction "IO_B5___N22/__DIFFIO_R32N/__DEV_OE_N22") (pintype "bidirectional"))
    )
    (net (code "34") (name "/24IO_I29") (class "Default")
      (node (ref "U2") (pin "P21") (pinfunction "IO_B5___P21/__DIFFIO_R38P/__DQ1R_P21") (pintype "bidirectional"))
    )
    (net (code "35") (name "/24IO_I30") (class "Default")
      (node (ref "U2") (pin "U20") (pinfunction "IO_B5___U20/__DIFFIO_R50N/__DQ3R_U20") (pintype "bidirectional"))
    )
    (net (code "36") (name "/24IO_I31") (class "Default")
      (node (ref "U2") (pin "U19") (pinfunction "IO_B5___U19/__DIFFIO_R50P_U19") (pintype "bidirectional"))
    )
    (net (code "37") (name "/24IO_I32") (class "Default")
      (node (ref "U2") (pin "F21") (pinfunction "IO_B6___F21/__DIFFIO_R18P/__DQ0R_F21") (pintype "bidirectional"))
    )
    (net (code "38") (name "/24IO_I33") (class "Default")
      (node (ref "U2") (pin "F22") (pinfunction "IO_B6___F22/__DIFFIO_R18N/__DQ0R_F22") (pintype "bidirectional"))
    )
    (net (code "39") (name "/24IO_I34") (class "Default")
      (node (ref "U2") (pin "G21") (pinfunction "CLK4___G21/__DIFFCLK_2P_G21") (pintype "bidirectional"))
    )
    (net (code "40") (name "/24IO_I35") (class "Default")
      (node (ref "U2") (pin "G22") (pinfunction "CLK5___G22/__DIFFCLK_2N_G22") (pintype "bidirectional"))
    )
    (net (code "41") (name "/24IO_I36") (class "Default")
      (node (ref "U2") (pin "H21") (pinfunction "IO_B6___H21/__DIFFIO_R22P/__DQ0R_H21") (pintype "bidirectional"))
    )
    (net (code "42") (name "/24IO_I37") (class "Default")
      (node (ref "U2") (pin "H22") (pinfunction "IO_B6___H22/__DIFFIO_R22N/__DQ0R_H22") (pintype "bidirectional"))
    )
    (net (code "43") (name "/24IO_I38") (class "Default")
      (node (ref "U2") (pin "J21") (pinfunction "IO_B6___J21/__DIFFIO_R23P/__DM0R_J21") (pintype "bidirectional"))
    )
    (net (code "44") (name "/24IO_I39") (class "Default")
      (node (ref "U2") (pin "J22") (pinfunction "IO_B6___J22/__DIFFIO_R23N/__DQS0R/CQ1R,DPCLK7_J22") (pintype "bidirectional"))
    )
    (net (code "45") (name "/24IO_I40") (class "Default")
      (node (ref "U2") (pin "P22") (pinfunction "IO_B5___P22/__DIFFIO_R38N/__DQ1R_P22") (pintype "bidirectional"))
    )
    (net (code "46") (name "/24IO_I41") (class "Default")
      (node (ref "U2") (pin "R21") (pinfunction "IO_B5___R21/__DIFFIO_R39P/__DQ1R_R21") (pintype "bidirectional"))
    )
    (net (code "47") (name "/24IO_I42") (class "Default")
      (node (ref "U2") (pin "R22") (pinfunction "IO_B5___R22/__DIFFIO_R39N/__DQ1R_R22") (pintype "bidirectional"))
    )
    (net (code "48") (name "/24IO_I43") (class "Default")
      (node (ref "U2") (pin "T22") (pinfunction "CLK7___T22/__DIFFCLK_3N_T22") (pintype "bidirectional"))
    )
    (net (code "49") (name "/24IO_I44") (class "Default")
      (node (ref "U2") (pin "U22") (pinfunction "IO_B5___U22/__DIFFIO_R43N/__DQ3R_U22") (pintype "bidirectional"))
    )
    (net (code "50") (name "/24IO_I45") (class "Default")
      (node (ref "U2") (pin "N16") (pinfunction "IO_B5___N16/__DIFFIO_R40P_N16") (pintype "bidirectional"))
    )
    (net (code "51") (name "/24IO_I46") (class "Default")
      (node (ref "U2") (pin "T17") (pinfunction "IO_B5___T17/__RUP3_T17") (pintype "bidirectional"))
    )
    (net (code "52") (name "/24IO_I47") (class "Default")
      (node (ref "U2") (pin "U21") (pinfunction "IO_B5___U21/__DIFFIO_R43P/__DQ3R_U21") (pintype "bidirectional"))
    )
    (net (code "53") (name "/24IO_I48") (class "Default")
      (node (ref "U2") (pin "B22") (pinfunction "IO_B6___B22/__DIFFIO_R5N/__PADD22/__DQ2R_B22") (pintype "bidirectional"))
    )
    (net (code "54") (name "/24IO_I49") (class "Default")
      (node (ref "U2") (pin "C21") (pinfunction "IO_B6___C21/__DIFFIO_R6P/__DQ2R_C21") (pintype "bidirectional"))
    )
    (net (code "55") (name "/24IO_I50") (class "Default")
      (node (ref "U2") (pin "E22") (pinfunction "IO_B6___E22/__DIFFIO_R12N/__NWE/__DQ0R_E22") (pintype "bidirectional"))
    )
    (net (code "56") (name "/24IO_I51") (class "Default")
      (node (ref "U2") (pin "D20") (pinfunction "VREFB6N0_D20") (pintype "bidirectional"))
    )
    (net (code "57") (name "/24IO_I52") (class "Default")
      (node (ref "U2") (pin "F19") (pinfunction "IO_B6___F19/__DIFFIO_R8P/__DQ2R_F19") (pintype "bidirectional"))
    )
    (net (code "58") (name "/24IO_I53") (class "Default")
      (node (ref "U2") (pin "F20") (pinfunction "IO_B6___F20/__DIFFIO_R8N/__NAVD/__DQ2R_F20") (pintype "bidirectional"))
    )
    (net (code "59") (name "/24IO_I54") (class "Default")
      (node (ref "U2") (pin "G17") (pinfunction "IO_B6___G17/__DIFFIO_R2P_G17") (pintype "bidirectional"))
    )
    (net (code "60") (name "/24IO_I55") (class "Default")
      (node (ref "U2") (pin "G18") (pinfunction "IO_B6___G18/__DIFFIO_R7N/__PADD23/__DQ2R_G18") (pintype "bidirectional"))
    )
    (net (code "61") (name "/24IO_I56") (class "Default")
      (node (ref "U2") (pin "P16") (pinfunction "IO_B5___P16/__DIFFIO_R46P_P16") (pintype "bidirectional"))
    )
    (net (code "62") (name "/24IO_I57") (class "Default")
      (node (ref "U2") (pin "R16") (pinfunction "IO_B4___R16/__PLL4_CLKOUTN_R16") (pintype "bidirectional"))
    )
    (net (code "63") (name "/24IO_I58") (class "Default")
      (node (ref "U2") (pin "P20") (pinfunction "VREFB5N1_P20") (pintype "bidirectional"))
    )
    (net (code "64") (name "/24IO_I59") (class "Default")
      (node (ref "U2") (pin "R19") (pinfunction "IO_B5___R19/__DIFFIO_R42P/__DM1R/BWS#1R_R19") (pintype "bidirectional"))
    )
    (net (code "65") (name "/24IO_I60") (class "Default")
      (node (ref "U2") (pin "R20") (pinfunction "IO_B5___R20/__DIFFIO_R44N/__DQ3R_R20") (pintype "bidirectional"))
    )
    (net (code "66") (name "/24IO_I61") (class "Default")
      (node (ref "U2") (pin "R18") (pinfunction "IO_B5___R18/__DIFFIO_R42N_R18") (pintype "bidirectional"))
    )
    (net (code "67") (name "/24IO_I62") (class "Default")
      (node (ref "U2") (pin "T18") (pinfunction "IO_B5___T18/__RDN3_T18") (pintype "bidirectional"))
    )
    (net (code "68") (name "/24IO_I63") (class "Default")
      (node (ref "U2") (pin "R17") (pinfunction "VREFB5N2_R17") (pintype "bidirectional"))
    )
    (net (code "69") (name "/AA5") (class "Default")
      (node (ref "DIPEX1") (pin "27") (pinfunction "27_27") (pintype "passive"))
      (node (ref "U2") (pin "AA5") (pinfunction "IO_B3___AA5/__DIFFIO_B8P/__DQ3B_AA5") (pintype "bidirectional"))
    )
    (net (code "70") (name "/AA7") (class "Default")
      (node (ref "DIPEX1") (pin "25") (pinfunction "25_25") (pintype "passive"))
      (node (ref "U2") (pin "AA7") (pinfunction "IO_B3___AA7/__DIFFIO_B14P/__DM5B/BWS#5B_AA7") (pintype "bidirectional"))
    )
    (net (code "71") (name "/AA8") (class "Default")
      (node (ref "DIPEX1") (pin "23") (pinfunction "23_23") (pintype "passive"))
      (node (ref "U2") (pin "AA8") (pinfunction "IO_B3___AA8/__DIFFIO_B18P/__DQ5B_AA8") (pintype "bidirectional"))
    )
    (net (code "72") (name "/AA9") (class "Default")
      (node (ref "DIPEX1") (pin "21") (pinfunction "21_21") (pintype "passive"))
      (node (ref "U2") (pin "AA9") (pinfunction "IO_B3___AA9/__DIFFIO_B21P/__DQ5B_AA9") (pintype "bidirectional"))
    )
    (net (code "73") (name "/AA10") (class "Default")
      (node (ref "DIPEX1") (pin "19") (pinfunction "19_19") (pintype "passive"))
      (node (ref "U2") (pin "AA10") (pinfunction "IO_B3___AA10/__DIFFIO_B27P/__DM4B_AA10") (pintype "bidirectional"))
    )
    (net (code "74") (name "/AA11") (class "Default")
      (node (ref "DIPEX1") (pin "18") (pinfunction "18_18") (pintype "passive"))
      (node (ref "U2") (pin "AA11") (pinfunction "CLK15___AA11/__DIFFCLK_6P_AA11") (pintype "bidirectional"))
    )
    (net (code "75") (name "/AA12") (class "Default")
      (node (ref "DIPEX1") (pin "16") (pinfunction "16_16") (pintype "passive"))
      (node (ref "U2") (pin "AA12") (pinfunction "CLK13___AA12/__DIFFCLK_7P_AA12") (pintype "bidirectional"))
    )
    (net (code "76") (name "/AA13") (class "Default")
      (node (ref "DIPEX1") (pin "14") (pinfunction "14_14") (pintype "passive"))
      (node (ref "U2") (pin "AA13") (pinfunction "IO_B4___AA13/__DIFFIO_B28P/__DQ4B_AA13") (pintype "bidirectional"))
    )
    (net (code "77") (name "/AA14") (class "Default")
      (node (ref "DIPEX1") (pin "12") (pinfunction "12_12") (pintype "passive"))
      (node (ref "U2") (pin "AA14") (pinfunction "IO_B4___AA14/__DIFFIO_B29P/__DQ4B_AA14") (pintype "bidirectional"))
    )
    (net (code "78") (name "/AA15") (class "Default")
      (node (ref "DIPEX1") (pin "10") (pinfunction "10_10") (pintype "passive"))
      (node (ref "U2") (pin "AA15") (pinfunction "IO_B4___AA15/__DIFFIO_B33P/__DQ4B_AA15") (pintype "bidirectional"))
    )
    (net (code "79") (name "/AA16") (class "Default")
      (node (ref "DIPEX1") (pin "8") (pinfunction "8_8") (pintype "passive"))
      (node (ref "U2") (pin "AA16") (pinfunction "IO_B4___AA16/__DIFFIO_B35P/__DM2B_AA16") (pintype "bidirectional"))
    )
    (net (code "80") (name "/AA17") (class "Default")
      (node (ref "DIPEX1") (pin "6") (pinfunction "6_6") (pintype "passive"))
      (node (ref "U2") (pin "AA17") (pinfunction "IO_B4___AA17/__DIFFIO_B43P_AA17") (pintype "bidirectional"))
    )
    (net (code "81") (name "/AA18") (class "Default")
      (node (ref "DIPEX1") (pin "4") (pinfunction "4_4") (pintype "passive"))
      (node (ref "U2") (pin "AA18") (pinfunction "VREFB4N1_AA18") (pintype "bidirectional"))
    )
    (net (code "82") (name "/AA19") (class "Default")
      (node (ref "DIPEX1") (pin "2") (pinfunction "2_2") (pintype "passive"))
      (node (ref "U2") (pin "AA19") (pinfunction "IO_B4___AA19/__RUP2_AA19") (pintype "bidirectional"))
    )
    (net (code "83") (name "/AA20") (class "Default")
      (node (ref "U2") (pin "AA20") (pinfunction "IO_B4___AA20/__DIFFIO_B49P_AA20") (pintype "bidirectional"))
    )
    (net (code "84") (name "/AB5") (class "Default")
      (node (ref "DIPEX1") (pin "28") (pinfunction "28_28") (pintype "passive"))
      (node (ref "U2") (pin "AB5") (pinfunction "IO_B3___AB5/__DIFFIO_B8N_AB5") (pintype "bidirectional"))
    )
    (net (code "85") (name "/AB7") (class "Default")
      (node (ref "DIPEX1") (pin "26") (pinfunction "26_26") (pintype "passive"))
      (node (ref "U2") (pin "AB7") (pinfunction "IO_B3___AB7/__DIFFIO_B14N/__DQ5B_AB7") (pintype "bidirectional"))
    )
    (net (code "86") (name "/AB8") (class "Default")
      (node (ref "DIPEX1") (pin "24") (pinfunction "24_24") (pintype "passive"))
      (node (ref "U2") (pin "AB8") (pinfunction "IO_B3___AB8/__DIFFIO_B18N/__DQ5B_AB8") (pintype "bidirectional"))
    )
    (net (code "87") (name "/AB9") (class "Default")
      (node (ref "DIPEX1") (pin "22") (pinfunction "22_22") (pintype "passive"))
      (node (ref "U2") (pin "AB9") (pinfunction "IO_B3___AB9/__DIFFIO_B21N/__DQS5B/CQ5B#,DPCLK3_AB9") (pintype "bidirectional"))
    )
    (net (code "88") (name "/AB10") (class "Default")
      (node (ref "DIPEX1") (pin "20") (pinfunction "20_20") (pintype "passive"))
      (node (ref "U2") (pin "AB10") (pinfunction "IO_B3___AB10/__DIFFIO_B27N_AB10") (pintype "bidirectional"))
    )
    (net (code "89") (name "/AB11") (class "Default")
      (node (ref "DIPEX1") (pin "17") (pinfunction "17_17") (pintype "passive"))
      (node (ref "U2") (pin "AB11") (pinfunction "CLK14___AB11/__DIFFCLK_6N_AB11") (pintype "bidirectional"))
    )
    (net (code "90") (name "/AB12") (class "Default")
      (node (ref "DIPEX1") (pin "15") (pinfunction "15_15") (pintype "passive"))
      (node (ref "U2") (pin "AB12") (pinfunction "CLK12___AB12/__DIFFCLK_7N_AB12") (pintype "bidirectional"))
    )
    (net (code "91") (name "/AB13") (class "Default")
      (node (ref "DIPEX1") (pin "13") (pinfunction "13_13") (pintype "passive"))
      (node (ref "U2") (pin "AB13") (pinfunction "IO_B4___AB13/__DIFFIO_B28N/__DQ4B_AB13") (pintype "bidirectional"))
    )
    (net (code "92") (name "/AB14") (class "Default")
      (node (ref "DIPEX1") (pin "11") (pinfunction "11_11") (pintype "passive"))
      (node (ref "U2") (pin "AB14") (pinfunction "IO_B4___AB14/__DIFFIO_B29N/__DQ4B_AB14") (pintype "bidirectional"))
    )
    (net (code "93") (name "/AB15") (class "Default")
      (node (ref "DIPEX1") (pin "9") (pinfunction "9_9") (pintype "passive"))
      (node (ref "U2") (pin "AB15") (pinfunction "IO_B4___AB15/__DIFFIO_B33N/__DQ4B_AB15") (pintype "bidirectional"))
    )
    (net (code "94") (name "/AB16") (class "Default")
      (node (ref "DIPEX1") (pin "7") (pinfunction "7_7") (pintype "passive"))
      (node (ref "U2") (pin "AB16") (pinfunction "IO_B4___AB16/__DIFFIO_B35N/__DQ2B_AB16") (pintype "bidirectional"))
    )
    (net (code "95") (name "/AB17") (class "Default")
      (node (ref "DIPEX1") (pin "5") (pinfunction "5_5") (pintype "passive"))
      (node (ref "U2") (pin "AB17") (pinfunction "IO_B4___AB17/__DIFFIO_B43N_AB17") (pintype "bidirectional"))
    )
    (net (code "96") (name "/AB18") (class "Default")
      (node (ref "DIPEX1") (pin "3") (pinfunction "3_3") (pintype "passive"))
      (node (ref "U2") (pin "AB18") (pinfunction "IO_B4___AB18/__DQ2B_AB18") (pintype "bidirectional"))
    )
    (net (code "97") (name "/AB19") (class "Default")
      (node (ref "DIPEX1") (pin "1") (pinfunction "1_1") (pintype "passive"))
      (node (ref "U2") (pin "AB19") (pinfunction "IO_B4___AB19/__RDN2_AB19") (pintype "bidirectional"))
    )
    (net (code "98") (name "/AB20") (class "Default")
      (node (ref "U2") (pin "AB20") (pinfunction "IO_B4___AB20/__DIFFIO_B49N/__DQ2B_AB20") (pintype "bidirectional"))
    )
    (net (code "99") (name "/AD_B") (class "Default")
      (node (ref "U2") (pin "Y21") (pinfunction "IO_B5___Y21/__DIFFIO_R51P_Y21") (pintype "bidirectional"))
    )
    (net (code "100") (name "/AD_BUSY") (class "Default")
      (node (ref "R151AD") (pin "2") (pinfunction "2_2") (pintype "passive"))
      (node (ref "R7AD") (pin "1") (pinfunction "1_1") (pintype "passive"))
    )
    (net (code "101") (name "/AD_CLK") (class "Default")
      (node (ref "R4AD") (pin "1") (pinfunction "1_1") (pintype "passive"))
      (node (ref "U1AD") (pin "19") (pinfunction "DCLK_19") (pintype "passive"))
      (node (ref "U2") (pin "V21") (pinfunction "IO_B5___V21/__DIFFIO_R45P/__DQ3R_V21") (pintype "bidirectional"))
    )
    (net (code "102") (name "/AD_CS") (class "Default")
      (node (ref "R5AD") (pin "1") (pinfunction "1_1") (pintype "passive"))
      (node (ref "U1AD") (pin "18") (pinfunction "~{CS}_18") (pintype "passive"))
      (node (ref "U2") (pin "V22") (pinfunction "IO_B5___V22/__DIFFIO_R45N/__DQ3R_V22") (pintype "bidirectional"))
    )
    (net (code "103") (name "/AD_DATA_IN") (class "Default")
      (node (ref "R6AD") (pin "1") (pinfunction "1_1") (pintype "passive"))
      (node (ref "U1AD") (pin "17") (pinfunction "DIN_17") (pintype "passive"))
      (node (ref "U2") (pin "W21") (pinfunction "IO_B5___W21/__DIFFIO_R49P/__DQ3R_W21") (pintype "bidirectional"))
    )
    (net (code "104") (name "/AD_DATA_O") (class "Default")
      (node (ref "U2") (pin "W22") (pinfunction "IO_B5___W22/__DIFFIO_R49N/__DQ3R_W22") (pintype "bidirectional"))
    )
    (net (code "105") (name "/AD_DATA_OUT") (class "Default")
      (node (ref "R8AD") (pin "1") (pinfunction "1_1") (pintype "passive"))
      (node (ref "R9AD") (pin "2") (pinfunction "2_2") (pintype "passive"))
    )
    (net (code "106") (name "/ASDO") (class "Default")
      (node (ref "U2") (pin "D1") (pinfunction "IO_B1___D1/__DIFFIO_L8N/__DATA1,ASDO_D1") (pintype "bidirectional"))
      (node (ref "U4") (pin "5") (pinfunction "D_5") (pintype "passive"))
    )
    (net (code "107") (name "/B1EX") (class "Default")
      (node (ref "DIPEX2") (pin "2") (pinfunction "2_2") (pintype "passive"))
      (node (ref "U2") (pin "B1") (pinfunction "IO_B1___B1/__DIFFIO_L2N/__DQ2L_B1") (pintype "bidirectional"))
    )
    (net (code "108") (name "/B2EX") (class "Default")
      (node (ref "DIPEX2") (pin "3") (pinfunction "3_3") (pintype "passive"))
      (node (ref "U2") (pin "B2") (pinfunction "IO_B1___B2/__DIFFIO_L2P/__DQ2L_B2") (pintype "bidirectional"))
    )
    (net (code "109") (name "/B3EX") (class "Default")
      (node (ref "DIPEX2") (pin "1") (pinfunction "1_1") (pintype "passive"))
      (node (ref "U2") (pin "B3") (pinfunction "IO_B8___B3/__DIFFIO_T4P/__DATA11/__DQ3T_B3") (pintype "bidirectional"))
    )
    (net (code "110") (name "/BT_RST") (class "Default")
      (node (ref "R542") (pin "2") (pinfunction "2_2") (pintype "passive"))
    )
    (net (code "111") (name "/C1") (class "Default")
      (node (ref "DIPEX2") (pin "4") (pinfunction "4_4") (pintype "passive"))
      (node (ref "U2") (pin "C1") (pinfunction "IO_B1___C1/__DIFFIO_L7N/__DQ2L_C1") (pintype "bidirectional"))
    )
    (net (code "112") (name "/C2") (class "Default")
      (node (ref "U2") (pin "C2") (pinfunction "IO_B1___C2/__DIFFIO_L7P/__DQS2L/CQ3L,CDPCLK0_C2") (pintype "bidirectional"))
    )
    (net (code "113") (name "/CH0") (class "Default")
      (node (ref "C5AD") (pin "1") (pinfunction "1_1") (pintype "passive"))
      (node (ref "R1252") (pin "2") (pinfunction "2_2") (pintype "passive"))
      (node (ref "R16AD") (pin "2") (pinfunction "2_2") (pintype "passive"))
      (node (ref "R23AD") (pin "1") (pinfunction "1_1") (pintype "passive"))
      (node (ref "U1AD") (pin "1") (pinfunction "CH0_1") (pintype "passive"))
    )
    (net (code "114") (name "/CH1") (class "Default")
      (node (ref "C6AD") (pin "1") (pinfunction "1_1") (pintype "passive"))
      (node (ref "R1264") (pin "2") (pinfunction "2_2") (pintype "passive"))
      (node (ref "R15AD") (pin "2") (pinfunction "2_2") (pintype "passive"))
      (node (ref "R22AD") (pin "1") (pinfunction "1_1") (pintype "passive"))
      (node (ref "U1AD") (pin "2") (pinfunction "CH1_2") (pintype "passive"))
    )
    (net (code "115") (name "/CH2") (class "Default")
      (node (ref "C7AD") (pin "1") (pinfunction "1_1") (pintype "passive"))
      (node (ref "R14AD") (pin "2") (pinfunction "2_2") (pintype "passive"))
      (node (ref "R21AD") (pin "1") (pinfunction "1_1") (pintype "passive"))
      (node (ref "R2252") (pin "2") (pinfunction "2_2") (pintype "passive"))
      (node (ref "U1AD") (pin "3") (pinfunction "CH2_3") (pintype "passive"))
    )
    (net (code "116") (name "/CH3") (class "Default")
      (node (ref "C8AD") (pin "1") (pinfunction "1_1") (pintype "passive"))
      (node (ref "R13AD") (pin "2") (pinfunction "2_2") (pintype "passive"))
      (node (ref "R20AD") (pin "1") (pinfunction "1_1") (pintype "passive"))
      (node (ref "R2264") (pin "2") (pinfunction "2_2") (pintype "passive"))
      (node (ref "U1AD") (pin "4") (pinfunction "CH3_4") (pintype "passive"))
    )
    (net (code "117") (name "/CH4") (class "Default")
      (node (ref "C9AD") (pin "1") (pinfunction "1_1") (pintype "passive"))
      (node (ref "R12AD") (pin "2") (pinfunction "2_2") (pintype "passive"))
      (node (ref "R19AD") (pin "1") (pinfunction "1_1") (pintype "passive"))
      (node (ref "U1AD") (pin "5") (pinfunction "CH4_5") (pintype "passive"))
    )
    (net (code "118") (name "/CH5") (class "Default")
      (node (ref "C10AD") (pin "1") (pinfunction "1_1") (pintype "passive"))
      (node (ref "R11AD") (pin "2") (pinfunction "2_2") (pintype "passive"))
      (node (ref "R18AD") (pin "1") (pinfunction "1_1") (pintype "passive"))
      (node (ref "U1AD") (pin "6") (pinfunction "CH5_6") (pintype "passive"))
    )
    (net (code "119") (name "/CH6") (class "Default")
      (node (ref "C11AD") (pin "1") (pinfunction "1_1") (pintype "passive"))
      (node (ref "R10AD") (pin "2") (pinfunction "2_2") (pintype "passive"))
      (node (ref "R17AD") (pin "1") (pinfunction "1_1") (pintype "passive"))
      (node (ref "U1AD") (pin "7") (pinfunction "CH6_7") (pintype "passive"))
    )
    (net (code "120") (name "/CLK_8M") (class "Default")
      (node (ref "U2") (pin "G1") (pinfunction "CLK1___G1/__DIFFCLK_0N_G1") (pintype "bidirectional"))
    )
    (net (code "121") (name "/CONFIG_DONE") (class "Default")
      (node (ref "R216") (pin "2") (pinfunction "2_2") (pintype "passive"))
      (node (ref "U2") (pin "M18") (pinfunction "CONF_DONE_M18") (pintype "bidirectional"))
    )
    (net (code "122") (name "/D2") (class "Default")
      (node (ref "DIPEX2") (pin "5") (pinfunction "5_5") (pintype "passive"))
      (node (ref "U2") (pin "D2") (pinfunction "IO_B1___D2/__DIFFIO_L8P/__DQ2L_D2") (pintype "bidirectional"))
    )
    (net (code "123") (name "/DA-0") (class "Default")
      (node (ref "R8DA") (pin "1") (pinfunction "1_1") (pintype "passive"))
      (node (ref "U2DA") (pin "2") (pinfunction "OUTA_2") (pintype "passive"))
      (node (ref "U3DA") (pin "3") (pinfunction "3_3") (pintype "passive"))
    )
    (net (code "124") (name "/DATA_OUT") (class "Default")
      (node (ref "R215") (pin "1") (pinfunction "1_1") (pintype "passive"))
      (node (ref "U2") (pin "K1") (pinfunction "IO_B1___K1/__DATA0_K1") (pintype "bidirectional"))
    )
    (net (code "125") (name "/DCLK") (class "Default")
      (node (ref "U2") (pin "K2") (pinfunction "DCLK_K2") (pintype "bidirectional"))
      (node (ref "U4") (pin "6") (pinfunction "C_6") (pintype "passive"))
    )
    (net (code "126") (name "/E1") (class "Default")
      (node (ref "DIPEX2") (pin "6") (pinfunction "6_6") (pintype "passive"))
      (node (ref "U2") (pin "E1") (pinfunction "IO_B1___E1/__DIFFIO_L10N_E1") (pintype "bidirectional"))
    )
    (net (code "127") (name "/E3") (class "Default")
      (node (ref "DIPEX2") (pin "14") (pinfunction "14_14") (pintype "passive"))
      (node (ref "U2") (pin "E3") (pinfunction "IO_B1___E3/__DIFFIO_L4N/__DQ2L_E3") (pintype "bidirectional"))
    )
    (net (code "128") (name "/E4") (class "Default")
      (node (ref "DIPEX2") (pin "17") (pinfunction "17_17") (pintype "passive"))
      (node (ref "U2") (pin "E4") (pinfunction "IO_B1___E4/__DIFFIO_L4P/__NRESET/__DQ2L_E4") (pintype "bidirectional"))
    )
    (net (code "129") (name "/F1") (class "Default")
      (node (ref "DIPEX2") (pin "8") (pinfunction "8_8") (pintype "passive"))
      (node (ref "U2") (pin "F1") (pinfunction "IO_B1___F1/__DIFFIO_L12N/__DQ0L_F1") (pintype "bidirectional"))
    )
    (net (code "130") (name "/F2") (class "Default")
      (node (ref "DIPEX2") (pin "7") (pinfunction "7_7") (pintype "passive"))
      (node (ref "U2") (pin "F2") (pinfunction "IO_B1___F2/__DIFFIO_L12P/__DM2L_F2") (pintype "bidirectional"))
    )
    (net (code "131") (name "/FPGA_LED9") (class "Default")
      (node (ref "LED11") (pin "2") (pinfunction "K_2") (pintype "passive"))
      (node (ref "U2") (pin "E6") (pinfunction "IO_B8___E6/__PLL3_CLKOUTN_E6") (pintype "bidirectional"))
    )
    (net (code "132") (name "/FPGA_LED10") (class "Default")
      (node (ref "LED12") (pin "2") (pinfunction "K_2") (pintype "passive"))
      (node (ref "U2") (pin "E5") (pinfunction "IO_B8___E5/__PLL3_CLKOUTP_E5") (pintype "bidirectional"))
    )
    (net (code "133") (name "/F_A1") (class "Default")
      (node (ref "U2") (pin "F16") (pinfunction "IO_B7___F16/__DIFFIO_T51N_F16") (pintype "bidirectional"))
    )
    (net (code "134") (name "/F_A2") (class "Default")
      (node (ref "U2") (pin "B19") (pinfunction "IO_B7___B19/__RUP4_B19") (pintype "bidirectional"))
    )
    (net (code "135") (name "/F_A3") (class "Default")
      (node (ref "U2") (pin "B10") (pinfunction "IO_B8___B10/__DIFFIO_T25P/__PADD15_B10") (pintype "bidirectional"))
    )
    (net (code "136") (name "/F_A4") (class "Default")
      (node (ref "U2") (pin "B12") (pinfunction "CLK9___B12/__DIFFCLK_5P_B12") (pintype "bidirectional"))
    )
    (net (code "137") (name "/F_A5") (class "Default")
      (node (ref "U2") (pin "A5") (pinfunction "IO_B8___A5/__DIFFIO_T11P/__DATA5/__DQ3T_A5") (pintype "bidirectional"))
    )
    (net (code "138") (name "/F_ALM1") (class "Default")
      (node (ref "U2") (pin "A17") (pinfunction "IO_B7___A17/__DIFFIO_T41N/__PADD1/__DQ2T_A17") (pintype "bidirectional"))
    )
    (net (code "139") (name "/F_ALM2") (class "Default")
      (node (ref "U2") (pin "F17") (pinfunction "IO_B6___F17/__DIFFIO_R2N/__DQ2R_F17") (pintype "bidirectional"))
    )
    (net (code "140") (name "/F_ALM3") (class "Default")
      (node (ref "U2") (pin "C8") (pinfunction "IO_B8___C8/__DIFFIO_T16N/__DATA14/__DQS3T/CQ3T#,DPCLK11_C8") (pintype "bidirectional"))
    )
    (net (code "141") (name "/F_ALM4") (class "Default")
      (node (ref "U2") (pin "B9") (pinfunction "IO_B8___B9/__DIFFIO_T24P/__PADD17/__DQS5T/CQ5T#,DPCLK10_B9") (pintype "bidirectional"))
    )
    (net (code "142") (name "/F_ALM5") (class "Default")
      (node (ref "U2") (pin "B6") (pinfunction "IO_B8___B6/__DIFFIO_T18P/__DATA15/__DQ5T_B6") (pintype "bidirectional"))
    )
    (net (code "143") (name "/F_B1") (class "Default")
      (node (ref "U2") (pin "A19") (pinfunction "IO_B7___A19/__RDN4_A19") (pintype "bidirectional"))
    )
    (net (code "144") (name "/F_B2") (class "Default")
      (node (ref "U2") (pin "A20") (pinfunction "IO_B7___A20/__PLL2_CLKOUTN_A20") (pintype "bidirectional"))
    )
    (net (code "145") (name "/F_B3") (class "Default")
      (node (ref "U2") (pin "A10") (pinfunction "IO_B8___A10/__DIFFIO_T25N/__DQ5T_A10") (pintype "bidirectional"))
    )
    (net (code "146") (name "/F_B4") (class "Default")
      (node (ref "U2") (pin "A12") (pinfunction "CLK8___A12/__DIFFCLK_5N_A12") (pintype "bidirectional"))
    )
    (net (code "147") (name "/F_B5") (class "Default")
      (node (ref "U2") (pin "B5") (pinfunction "VREFB8N2_B5") (pintype "bidirectional"))
    )
    (net (code "148") (name "/F_CON1") (class "Default")
      (node (ref "U2") (pin "B17") (pinfunction "IO_B7___B17/__DIFFIO_T41P/__PADD2_B17") (pintype "bidirectional"))
    )
    (net (code "149") (name "/F_CON2") (class "Default")
      (node (ref "U2") (pin "C17") (pinfunction "IO_B7___C17/__DIFFIO_T46P/__DQ2T_C17") (pintype "bidirectional"))
    )
    (net (code "150") (name "/F_CON3") (class "Default")
      (node (ref "U2") (pin "G9") (pinfunction "IO_B8___G9_G9") (pintype "bidirectional"))
    )
    (net (code "151") (name "/F_CON4") (class "Default")
      (node (ref "U2") (pin "A9") (pinfunction "IO_B8___A9/__DIFFIO_T24N/__PADD16/__DQ5T_A9") (pintype "bidirectional"))
    )
    (net (code "152") (name "/F_CON5") (class "Default")
      (node (ref "U2") (pin "A6") (pinfunction "IO_B8___A6/__DIFFIO_T18N/__PADD19/__DQ5T_A6") (pintype "bidirectional"))
    )
    (net (code "153") (name "/F_NEG1") (class "Default")
      (node (ref "U2") (pin "B15") (pinfunction "IO_B7___B15/__DIFFIO_T36P/__PADD6/__DQ4T_B15") (pintype "bidirectional"))
    )
    (net (code "154") (name "/F_NEG2") (class "Default")
      (node (ref "U2") (pin "E16") (pinfunction "IO_B7___E16/__DIFFIO_T51P/__DQ2T_E16") (pintype "bidirectional"))
    )
    (net (code "155") (name "/F_NEG3") (class "Default")
      (node (ref "U2") (pin "E7") (pinfunction "IO_B8___E7_E7") (pintype "bidirectional"))
    )
    (net (code "156") (name "/F_NEG4") (class "Default")
      (node (ref "U2") (pin "C7") (pinfunction "IO_B8___C7/__DIFFIO_T16P/__DATA13/__DM5T/BWS#5T_C7") (pintype "bidirectional"))
    )
    (net (code "157") (name "/F_NEG5") (class "Default")
      (node (ref "U2") (pin "A8") (pinfunction "IO_B8___A8/__DIFFIO_T20N/__DATA2/__DQ5T_A8") (pintype "bidirectional"))
    )
    (net (code "158") (name "/F_POS1") (class "Default")
      (node (ref "U2") (pin "A15") (pinfunction "IO_B7___A15/__DIFFIO_T36N/__PADD5/__DQ4T_A15") (pintype "bidirectional"))
    )
    (net (code "159") (name "/F_POS2") (class "Default")
      (node (ref "U2") (pin "D17") (pinfunction "VREFB7N0_D17") (pintype "bidirectional"))
    )
    (net (code "160") (name "/F_POS3") (class "Default")
      (node (ref "U2") (pin "F7") (pinfunction "IO_B8___F7/__DIFFIO_T1N/__DM3T/BWS#3T_F7") (pintype "bidirectional"))
    )
    (net (code "161") (name "/F_POS4") (class "Default")
      (node (ref "U2") (pin "D7") (pinfunction "IO_B8___D7/__DIFFIO_T7P_D7") (pintype "bidirectional"))
    )
    (net (code "162") (name "/F_POS5") (class "Default")
      (node (ref "U2") (pin "B8") (pinfunction "IO_B8___B8/__DIFFIO_T20P/__DATA3/__DQ5T_B8") (pintype "bidirectional"))
    )
    (net (code "163") (name "/F_PW1") (class "Default")
      (node (ref "U2") (pin "U14") (pinfunction "IO_B4___U14/__DIFFIO_B39N_U14") (pintype "bidirectional"))
    )
    (net (code "164") (name "/F_PW2") (class "Default")
      (node (ref "U2") (pin "U13") (pinfunction "IO_B4___U13/__DIFFIO_B38N_U13") (pintype "bidirectional"))
    )
    (net (code "165") (name "/F_R1") (class "Default")
      (node (ref "U2") (pin "F15") (pinfunction "IO_B7___F15/__DIFFIO_T50N/__DQ2T_F15") (pintype "bidirectional"))
    )
    (net (code "166") (name "/F_R2") (class "Default")
      (node (ref "U2") (pin "B20") (pinfunction "IO_B7___B20/__PLL2_CLKOUTP_B20") (pintype "bidirectional"))
    )
    (net (code "167") (name "/F_R3") (class "Default")
      (node (ref "U2") (pin "B11") (pinfunction "CLK11___B11/__DIFFCLK_4P_B11") (pintype "bidirectional"))
    )
    (net (code "168") (name "/F_R4") (class "Default")
      (node (ref "U2") (pin "B13") (pinfunction "IO_B7___B13/__DIFFIO_T29P/__PADD12/__DQS4T/CQ5T,DPCLK9_B13") (pintype "bidirectional"))
    )
    (net (code "169") (name "/F_R5") (class "Default")
      (node (ref "U2") (pin "B4") (pinfunction "IO_B8___B4/__DIFFIO_T6P/__DATA8/__DQ3T_B4") (pintype "bidirectional"))
    )
    (net (code "170") (name "/F_S1") (class "Default")
      (node (ref "U2") (pin "F14") (pinfunction "IO_B7___F14/__DIFFIO_T49P/__DQS0T/CQ1T,CDPCLK6_F14") (pintype "bidirectional"))
    )
    (net (code "171") (name "/F_S2") (class "Default")
      (node (ref "U2") (pin "B21") (pinfunction "IO_B6___B21/__DIFFIO_R5P/__PADD21/__DQ2R_B21") (pintype "bidirectional"))
    )
    (net (code "172") (name "/F_S3") (class "Default")
      (node (ref "U2") (pin "A11") (pinfunction "CLK10___A11/__DIFFCLK_4N_A11") (pintype "bidirectional"))
    )
    (net (code "173") (name "/F_S4") (class "Default")
      (node (ref "U2") (pin "A13") (pinfunction "IO_B7___A13/__DIFFIO_T29N/__PADD11/__DQ4T_A13") (pintype "bidirectional"))
    )
    (net (code "174") (name "/F_S5") (class "Default")
      (node (ref "U2") (pin "A4") (pinfunction "IO_B8___A4/__DIFFIO_T6N/__DQ3T_A4") (pintype "bidirectional"))
    )
    (net (code "175") (name "/F_SEN1") (class "Default")
      (node (ref "U2") (pin "G10") (pinfunction "IO_B8___G10/__DIFFIO_T8N_G10") (pintype "bidirectional"))
    )
    (net (code "176") (name "/F_SEN2") (class "Default")
      (node (ref "U2") (pin "F10") (pinfunction "IO_B8___F10/__DIFFIO_T8P/__DATA6/__DQ3T_F10") (pintype "bidirectional"))
    )
    (net (code "177") (name "/F_SEN3") (class "Default")
      (node (ref "U2") (pin "E10") (pinfunction "IO_B8___E10/__DIFFIO_T26P_E10") (pintype "bidirectional"))
    )
    (net (code "178") (name "/F_SEN4") (class "Default")
      (node (ref "U2") (pin "F11") (pinfunction "IO_B7___F11/__DIFFIO_T27P/__PADD14/__DM4T_F11") (pintype "bidirectional"))
    )
    (net (code "179") (name "/F_SEN5") (class "Default")
      (node (ref "U2") (pin "F13") (pinfunction "IO_B7___F13/__DIFFIO_T37P/__PADD4/__DQS2T/CQ3T,DPCLK8_F13") (pintype "bidirectional"))
    )
    (net (code "180") (name "/F_SON1") (class "Default")
      (node (ref "U2") (pin "A16") (pinfunction "IO_B7___A16/__DIFFIO_T40N/__DM2T_A16") (pintype "bidirectional"))
    )
    (net (code "181") (name "/F_SON2") (class "Default")
      (node (ref "U2") (pin "B16") (pinfunction "IO_B7___B16/__DIFFIO_T40P/__DQ4T_B16") (pintype "bidirectional"))
    )
    (net (code "182") (name "/F_SON3") (class "Default")
      (node (ref "U2") (pin "F9") (pinfunction "IO_B8___F9_F9") (pintype "bidirectional"))
    )
    (net (code "183") (name "/F_SON4") (class "Default")
      (node (ref "U2") (pin "G8") (pinfunction "IO_B8___G8/__DIFFIO_T5P_G8") (pintype "bidirectional"))
    )
    (net (code "184") (name "/F_SON5") (class "Default")
      (node (ref "U2") (pin "A7") (pinfunction "IO_B8___A7/__DIFFIO_T19N/__PADD18/__DQ5T_A7") (pintype "bidirectional"))
    )
    (net (code "185") (name "/G3") (class "Default")
      (node (ref "DIPEX2") (pin "9") (pinfunction "9_9") (pintype "passive"))
      (node (ref "U2") (pin "G3") (pinfunction "IO_B1___G3/__DIFFIO_L1N_G3") (pintype "bidirectional"))
    )
    (net (code "186") (name "/G4") (class "Default")
      (node (ref "DIPEX2") (pin "18") (pinfunction "18_18") (pintype "passive"))
      (node (ref "U2") (pin "G4") (pinfunction "IO_B1___G4/__DIFFIO_L1P_G4") (pintype "bidirectional"))
    )
    (net (code "187") (name "/G5") (class "Default")
      (node (ref "DIPEX2") (pin "19") (pinfunction "19_19") (pintype "passive"))
      (node (ref "U2") (pin "G5") (pinfunction "VREFB1N0_G5") (pintype "bidirectional"))
    )
    (net (code "188") (name "/G7") (class "Default")
      (node (ref "DIPEX2") (pin "15") (pinfunction "15_15") (pintype "passive"))
      (node (ref "U2") (pin "G7") (pinfunction "IO_B8___G7/__DIFFIO_T1P_G7") (pintype "bidirectional"))
    )
    (net (code "189") (name "/GP0_21") (class "Default")
      (node (ref "U2") (pin "M2") (pinfunction "IO_B2___M2/__DIFFIO_L27P/__DQ0L_M2") (pintype "bidirectional"))
    )
    (net (code "190") (name "/GP0_23") (class "Default")
      (node (ref "U2") (pin "M1") (pinfunction "IO_B2___M1/__DIFFIO_L27N_M1") (pintype "bidirectional"))
    )
    (net (code "191") (name "/GP0_24") (class "Default")
      (node (ref "U2") (pin "M3") (pinfunction "IO_B2___M3/__DIFFIO_L28N/__DQ1L_M3") (pintype "bidirectional"))
    )
    (net (code "192") (name "/GP0_31") (class "Default")
      (node (ref "U2") (pin "L6") (pinfunction "IO_B2___L6/__DIFFIO_L26P/__DQ0L_L6") (pintype "bidirectional"))
    )
    (net (code "193") (name "/GPMC_A0") (class "Default")
      (node (ref "U2") (pin "Y2") (pinfunction "IO_B2___Y2/__DIFFIO_L45P/__DQ3L_Y2") (pintype "bidirectional"))
    )
    (net (code "194") (name "/GPMC_A1") (class "Default")
      (node (ref "U2") (pin "W6") (pinfunction "IO_B3___W6/__DIFFIO_B7P/__DQ3B_W6") (pintype "bidirectional"))
    )
    (net (code "195") (name "/GPMC_A2") (class "Default")
      (node (ref "U2") (pin "W2") (pinfunction "IO_B2___W2/__DIFFIO_L44P/__DQ3L_W2") (pintype "bidirectional"))
    )
    (net (code "196") (name "/GPMC_A3") (class "Default")
      (node (ref "U2") (pin "V5") (pinfunction "IO_B3___V5/__DIFFIO_B1N/__DM3B/BWS#3B_V5") (pintype "bidirectional"))
    )
    (net (code "197") (name "/GPMC_A4") (class "Default")
      (node (ref "U2") (pin "W1") (pinfunction "IO_B2___W1/__DIFFIO_L44N/__DQ3L_W1") (pintype "bidirectional"))
    )
    (net (code "198") (name "/GPMC_A5") (class "Default")
      (node (ref "U2") (pin "V4") (pinfunction "IO_B2___V4/__RUP1_V4") (pintype "bidirectional"))
    )
    (net (code "199") (name "/GPMC_A6") (class "Default")
      (node (ref "U2") (pin "V3") (pinfunction "IO_B2___V3/__RDN1_V3") (pintype "bidirectional"))
    )
    (net (code "200") (name "/GPMC_A7") (class "Default")
      (node (ref "U2") (pin "V6") (pinfunction "IO_B3___V6/__DIFFIO_B1P_V6") (pintype "bidirectional"))
    )
    (net (code "201") (name "/GPMC_A8") (class "Default")
      (node (ref "U2") (pin "U7") (pinfunction "IO_B3___U7/__DIFFIO_B3P_U7") (pintype "bidirectional"))
    )
    (net (code "202") (name "/GPMC_A9") (class "Default")
      (node (ref "U2") (pin "V1") (pinfunction "IO_B2___V1/__DIFFIO_L38N/__DQ3L_V1") (pintype "bidirectional"))
    )
    (net (code "203") (name "/GPMC_A10") (class "Default")
      (node (ref "U2") (pin "R6") (pinfunction "IO_B2___R6_R6") (pintype "bidirectional"))
    )
    (net (code "204") (name "/GPMC_A11") (class "Default")
      (node (ref "U2") (pin "U2") (pinfunction "IO_B2___U2/__DIFFIO_L35P/__DM1L/BWS#1L_U2") (pintype "bidirectional"))
    )
    (net (code "205") (name "/GPMC_A12") (class "Default")
      (node (ref "U2") (pin "AA1") (pinfunction "IO_B2___AA1/__DIFFIO_L50N/__DQ3L_AA1") (pintype "bidirectional"))
    )
    (net (code "206") (name "/GPMC_CLK") (class "Default")
      (node (ref "U2") (pin "T2") (pinfunction "CLK2___T2/__DIFFCLK_1P_T2") (pintype "bidirectional"))
    )
    (net (code "207") (name "/GPMC_CS1") (class "Default")
      (node (ref "U2") (pin "AA3") (pinfunction "IO_B3___AA3/__PLL1_CLKOUTP_AA3") (pintype "bidirectional"))
    )
    (net (code "208") (name "/GPMC_CS2") (class "Default")
      (node (ref "U2") (pin "AA4") (pinfunction "IO_B3___AA4/__DQ3B_AA4") (pintype "bidirectional"))
    )
    (net (code "209") (name "/GPMC_D0") (class "Default")
      (node (ref "U2") (pin "R5") (pinfunction "VREFB2N3_R5") (pintype "bidirectional"))
    )
    (net (code "210") (name "/GPMC_D1") (class "Default")
      (node (ref "U2") (pin "T5") (pinfunction "IO_B2___T5/__DM3L/BWS#3L_T5") (pintype "bidirectional"))
    )
    (net (code "211") (name "/GPMC_D2") (class "Default")
      (node (ref "U2") (pin "M5") (pinfunction "VREFB2N0_M5") (pintype "bidirectional"))
    )
    (net (code "212") (name "/GPMC_D3") (class "Default")
      (node (ref "U2") (pin "U1") (pinfunction "IO_B2___U1/__DIFFIO_L35N/__DQ3L_U1") (pintype "bidirectional"))
    )
    (net (code "213") (name "/GPMC_D4") (class "Default")
      (node (ref "U2") (pin "R1") (pinfunction "IO_B2___R1/__DIFFIO_L33N/__DQ1L_R1") (pintype "bidirectional"))
    )
    (net (code "214") (name "/GPMC_D5") (class "Default")
      (node (ref "U2") (pin "R2") (pinfunction "IO_B2___R2/__DIFFIO_L33P/__DQ1L_R2") (pintype "bidirectional"))
    )
    (net (code "215") (name "/GPMC_D6") (class "Default")
      (node (ref "U2") (pin "P5") (pinfunction "VREFB2N1_P5") (pintype "bidirectional"))
    )
    (net (code "216") (name "/GPMC_D7") (class "Default")
      (node (ref "U2") (pin "P4") (pinfunction "IO_B2___P4/__DIFFIO_L34P/__DQS1L/CQ1L#,DPCLK1_P4") (pintype "bidirectional"))
    )
    (net (code "217") (name "/GPMC_D8") (class "Default")
      (node (ref "U2") (pin "M4") (pinfunction "IO_B2___M4/__DIFFIO_L28P/__DM0L_M4") (pintype "bidirectional"))
    )
    (net (code "218") (name "/GPMC_D9") (class "Default")
      (node (ref "U2") (pin "P1") (pinfunction "IO_B2___P1/__DIFFIO_L32N/__DQ1L_P1") (pintype "bidirectional"))
    )
    (net (code "219") (name "/GPMC_D10") (class "Default")
      (node (ref "U2") (pin "N1") (pinfunction "IO_B2___N1/__DIFFIO_L29N/__DQ1L_N1") (pintype "bidirectional"))
    )
    (net (code "220") (name "/GPMC_D11") (class "Default")
      (node (ref "U2") (pin "AB4") (pinfunction "VREFB3N2_AB4") (pintype "bidirectional"))
    )
    (net (code "221") (name "/GPMC_D12") (class "Default")
      (node (ref "U2") (pin "T3") (pinfunction "VREFB2N2_T3") (pintype "bidirectional"))
    )
    (net (code "222") (name "/GPMC_D13") (class "Default")
      (node (ref "U2") (pin "P2") (pinfunction "IO_B2___P2/__DIFFIO_L32P/__DQ1L_P2") (pintype "bidirectional"))
    )
    (net (code "223") (name "/GPMC_D14") (class "Default")
      (node (ref "U2") (pin "N2") (pinfunction "IO_B2___N2/__DIFFIO_L29P/__DQ1L_N2") (pintype "bidirectional"))
    )
    (net (code "224") (name "/GPMC_D15") (class "Default")
      (node (ref "U2") (pin "T4") (pinfunction "IO_B2___T4/__DQS3L/CQ3L#,CDPCLK1_T4") (pintype "bidirectional"))
    )
    (net (code "225") (name "/GPMC_REN") (class "Default")
      (node (ref "U2") (pin "Y1") (pinfunction "IO_B2___Y1/__DIFFIO_L45N/__DQ3L_Y1") (pintype "bidirectional"))
    )
    (net (code "226") (name "/GPMC_WEN") (class "Default")
      (node (ref "U2") (pin "AB3") (pinfunction "IO_B3___AB3/__PLL1_CLKOUTN_AB3") (pintype "bidirectional"))
    )
    (net (code "227") (name "/H1") (class "Default")
      (node (ref "DIPEX2") (pin "12") (pinfunction "12_12") (pintype "passive"))
      (node (ref "U2") (pin "H1") (pinfunction "IO_B1___H1/__DIFFIO_L23N/__DQ0L_H1") (pintype "bidirectional"))
    )
    (net (code "228") (name "/H2") (class "Default")
      (node (ref "DIPEX2") (pin "11") (pinfunction "11_11") (pintype "passive"))
      (node (ref "U2") (pin "H2") (pinfunction "IO_B1___H2/__DIFFIO_L23P/__DQ0L_H2") (pintype "bidirectional"))
    )
    (net (code "229") (name "/H5") (class "Default")
      (node (ref "DIPEX2") (pin "10") (pinfunction "10_10") (pintype "passive"))
      (node (ref "U2") (pin "H5") (pinfunction "VREFB1N2_H5") (pintype "bidirectional"))
    )
    (net (code "230") (name "/H7") (class "Default")
      (node (ref "DIPEX2") (pin "16") (pinfunction "16_16") (pintype "passive"))
      (node (ref "U2") (pin "H7") (pinfunction "VREFB1N1_H7") (pintype "bidirectional"))
    )
    (net (code "231") (name "/J1") (class "Default")
      (node (ref "DIPEX2") (pin "24") (pinfunction "24_24") (pintype "passive"))
      (node (ref "U2") (pin "J1") (pinfunction "IO_B1___J1/__DIFFIO_L24N/__DQ0L_J1") (pintype "bidirectional"))
    )
    (net (code "232") (name "/J2") (class "Default")
      (node (ref "DIPEX2") (pin "23") (pinfunction "23_23") (pintype "passive"))
      (node (ref "U2") (pin "J2") (pinfunction "IO_B1___J2/__DIFFIO_L24P/__DQ0L_J2") (pintype "bidirectional"))
    )
    (net (code "233") (name "/J3") (class "Default")
      (node (ref "DIPEX2") (pin "20") (pinfunction "20_20") (pintype "passive"))
      (node (ref "U2") (pin "J3") (pinfunction "VREFB1N3_J3") (pintype "bidirectional"))
    )
    (net (code "234") (name "/J4") (class "Default")
      (node (ref "DIPEX2") (pin "21") (pinfunction "21_21") (pintype "passive"))
      (node (ref "U2") (pin "J4") (pinfunction "IO_B1___J4/__DQS0L/CQ1L,DPCLK0_J4") (pintype "bidirectional"))
    )
    (net (code "235") (name "/J5") (class "Default")
      (node (ref "DIPEX2") (pin "22") (pinfunction "22_22") (pintype "passive"))
      (node (ref "U2") (pin "J5") (pinfunction "IO_B1___J5/__DIFFIO_L18N_J5") (pintype "bidirectional"))
    )
    (net (code "236") (name "/J6") (class "Default")
      (node (ref "U2") (pin "J6") (pinfunction "IO_B1___J6/__DIFFIO_L9N/__DQ2L_J6") (pintype "bidirectional"))
    )
    (net (code "237") (name "/J7") (class "Default")
      (node (ref "DIPEX2") (pin "13") (pinfunction "13_13") (pintype "passive"))
      (node (ref "U2") (pin "J7") (pinfunction "IO_B1___J7/__DIFFIO_L21P_J7") (pintype "bidirectional"))
    )
    (net (code "238") (name "/K7") (class "Default")
      (node (ref "DIPEX2") (pin "26") (pinfunction "26_26") (pintype "passive"))
      (node (ref "U2") (pin "K7") (pinfunction "IO_B1___K7/__DIFFIO_L21N_K7") (pintype "bidirectional"))
    )
    (net (code "239") (name "/K8") (class "Default")
      (node (ref "DIPEX2") (pin "25") (pinfunction "25_25") (pintype "passive"))
      (node (ref "U2") (pin "K8") (pinfunction "IO_B1___K8/__DIFFIO_L20N_K8") (pintype "bidirectional"))
    )
    (net (code "240") (name "/L358_5") (class "Default")
      (node (ref "R1260") (pin "2") (pinfunction "2_2") (pintype "passive"))
      (node (ref "U148") (pin "5") (pinfunction "INPOUT2+_5") (pintype "passive"))
    )
    (net (code "241") (name "/L358_6") (class "Default")
      (node (ref "R1259") (pin "2") (pinfunction "2_2") (pintype "passive"))
      (node (ref "R1262") (pin "1") (pinfunction "1_1") (pintype "passive"))
      (node (ref "U148") (pin "6") (pinfunction "INPUT2-_6") (pintype "passive"))
    )
    (net (code "242") (name "/L358_7") (class "Default")
      (node (ref "R1262") (pin "2") (pinfunction "2_2") (pintype "passive"))
      (node (ref "R1264") (pin "1") (pinfunction "1_1") (pintype "passive"))
      (node (ref "U148") (pin "7") (pinfunction "OUTPUT2_7") (pintype "passive"))
    )
    (net (code "243") (name "/LM358_5") (class "Default")
      (node (ref "R2260") (pin "2") (pinfunction "2_2") (pintype "passive"))
      (node (ref "U247") (pin "5") (pinfunction "INPOUT2+_5") (pintype "passive"))
    )
    (net (code "244") (name "/LM358_6") (class "Default")
      (node (ref "R2259") (pin "2") (pinfunction "2_2") (pintype "passive"))
      (node (ref "R2262") (pin "1") (pinfunction "1_1") (pintype "passive"))
      (node (ref "U247") (pin "6") (pinfunction "INPUT2-_6") (pintype "passive"))
    )
    (net (code "245") (name "/LM358_7") (class "Default")
      (node (ref "R2262") (pin "2") (pinfunction "2_2") (pintype "passive"))
      (node (ref "R2264") (pin "1") (pinfunction "1_1") (pintype "passive"))
      (node (ref "U247") (pin "7") (pinfunction "OUTPUT2_7") (pintype "passive"))
    )
    (net (code "246") (name "/PULSE1") (class "Default")
      (node (ref "U2") (pin "B18") (pinfunction "IO_B7___B18/__DIFFIO_T45P/__PADD0_B18") (pintype "bidirectional"))
    )
    (net (code "247") (name "/PULSE2") (class "Default")
      (node (ref "U2") (pin "B14") (pinfunction "IO_B7___B14/__DIFFIO_T31P/__PADD10/__DQ4T_B14") (pintype "bidirectional"))
    )
    (net (code "248") (name "/PULSE3") (class "Default")
      (node (ref "U2") (pin "C15") (pinfunction "VREFB7N2_C15") (pintype "bidirectional"))
    )
    (net (code "249") (name "/PULSE4") (class "Default")
      (node (ref "U2") (pin "E14") (pinfunction "IO_B7___E14/__DIFFIO_T38N/__PADD3/__DQ4T_E14") (pintype "bidirectional"))
    )
    (net (code "250") (name "/PULSE5") (class "Default")
      (node (ref "U2") (pin "C6") (pinfunction "IO_B8___C6/__DIFFIO_T7N/__DATA7/__DQ3T_C6") (pintype "bidirectional"))
    )
    (net (code "251") (name "/Pt1000_A_1") (class "Default")
      (node (ref "PT1000_A") (pin "1") (pinfunction "1_1") (pintype "passive"))
      (node (ref "R1247") (pin "2") (pinfunction "2_2") (pintype "passive"))
      (node (ref "R1248") (pin "1") (pinfunction "1_1") (pintype "passive"))
    )
    (net (code "252") (name "/Pt1000_A_2") (class "Default")
      (node (ref "PT1000_A") (pin "3") (pinfunction "3_3") (pintype "passive"))
      (node (ref "R1257") (pin "2") (pinfunction "2_2") (pintype "passive"))
      (node (ref "R1258") (pin "1") (pinfunction "1_1") (pintype "passive"))
    )
    (net (code "253") (name "/Pt1000_B_1") (class "Default")
      (node (ref "PT1000_B") (pin "1") (pinfunction "1_1") (pintype "passive"))
      (node (ref "R2247") (pin "2") (pinfunction "2_2") (pintype "passive"))
      (node (ref "R2248") (pin "1") (pinfunction "1_1") (pintype "passive"))
    )
    (net (code "254") (name "/Pt1000_B_2") (class "Default")
      (node (ref "PT1000_B") (pin "3") (pinfunction "3_3") (pintype "passive"))
      (node (ref "R2257") (pin "2") (pinfunction "2_2") (pintype "passive"))
      (node (ref "R2258") (pin "1") (pinfunction "1_1") (pintype "passive"))
    )
    (net (code "255") (name "/SCL_DA") (class "Default")
      (node (ref "R5DA") (pin "2") (pinfunction "2_2") (pintype "passive"))
      (node (ref "U2DA") (pin "9") (pinfunction "SCL_9") (pintype "passive"))
    )
    (net (code "256") (name "/SCL_LED") (class "Default")
      (node (ref "U2") (pin "U10") (pinfunction "IO_B3___U10/__DIFFIO_B17N/__DQ5B_U10") (pintype "bidirectional"))
    )
    (net (code "257") (name "/SDA_DA") (class "Default")
      (node (ref "R4DA") (pin "2") (pinfunction "2_2") (pintype "passive"))
      (node (ref "U2DA") (pin "8") (pinfunction "SDA_8") (pintype "passive"))
    )
    (net (code "258") (name "/SDA_LED") (class "Default")
      (node (ref "U2") (pin "R15") (pinfunction "IO_B4___R15/__DIFFIO_B52N_R15") (pintype "bidirectional"))
    )
    (net (code "259") (name "/SIGN1") (class "Default")
      (node (ref "U2") (pin "A18") (pinfunction "IO_B7___A18/__DIFFIO_T45N/__DQ2T_A18") (pintype "bidirectional"))
    )
    (net (code "260") (name "/SIGN2") (class "Default")
      (node (ref "U2") (pin "A14") (pinfunction "IO_B7___A14/__DIFFIO_T31N/__PADD9/__DQ4T_A14") (pintype "bidirectional"))
    )
    (net (code "261") (name "/SIGN3") (class "Default")
      (node (ref "U2") (pin "D15") (pinfunction "VREFB7N1_D15") (pintype "bidirectional"))
    )
    (net (code "262") (name "/SIGN4") (class "Default")
      (node (ref "U2") (pin "E15") (pinfunction "IO_B7___E15/__DIFFIO_T44N/__DQ2T_E15") (pintype "bidirectional"))
    )
    (net (code "263") (name "/SIGN5") (class "Default")
      (node (ref "U2") (pin "D6") (pinfunction "VREFB8N3_D6") (pintype "bidirectional"))
    )
    (net (code "264") (name "/TCK_F") (class "Default")
      (node (ref "J11") (pin "4") (pinfunction "4_4") (pintype "passive"))
      (node (ref "R213") (pin "2") (pinfunction "2_2") (pintype "passive"))
      (node (ref "U2") (pin "L2") (pinfunction "TCK_L2") (pintype "bidirectional"))
    )
    (net (code "265") (name "/TDI_F") (class "Default")
      (node (ref "J11") (pin "2") (pinfunction "2_2") (pintype "passive"))
      (node (ref "R212") (pin "2") (pinfunction "2_2") (pintype "passive"))
      (node (ref "U2") (pin "L5") (pinfunction "TDI_L5") (pintype "bidirectional"))
    )
    (net (code "266") (name "/TDO_F") (class "Default")
      (node (ref "J11") (pin "3") (pinfunction "3_3") (pintype "passive"))
      (node (ref "U2") (pin "L4") (pinfunction "TDO_L4") (pintype "bidirectional"))
    )
    (net (code "267") (name "/TMS_F") (class "Default")
      (node (ref "J11") (pin "5") (pinfunction "5_5") (pintype "passive"))
      (node (ref "R214") (pin "1") (pinfunction "1_1") (pintype "passive"))
      (node (ref "U2") (pin "L1") (pinfunction "TMS_L1") (pintype "bidirectional"))
    )
    (net (code "268") (name "/VDD_24V_SYSTEM") (class "Default")
      (node (ref "DIPEX1") (pin "29") (pinfunction "29_29") (pintype "passive"))
      (node (ref "DIPEX2") (pin "30") (pinfunction "30_30") (pintype "passive"))
    )
    (net (code "269") (name "/Y17") (class "Default")
      (node (ref "U2") (pin "Y17") (pinfunction "IO_B4___Y17/__DIFFIO_B48N/__DQS0B/CQ1B,CDPCLK3_Y17") (pintype "bidirectional"))
    )
    (net (code "270") (name "/Y22") (class "Default")
      (node (ref "U2") (pin "Y22") (pinfunction "IO_B5___Y22/__DIFFIO_R51N/__DQ3R_Y22") (pintype "bidirectional"))
    )
    (net (code "271") (name "/nCE") (class "Default")
      (node (ref "R217") (pin "2") (pinfunction "2_2") (pintype "passive"))
      (node (ref "U2") (pin "L3") (pinfunction "NCE_L3") (pintype "bidirectional"))
    )
    (net (code "272") (name "/nCONFIG") (class "Default")
      (node (ref "R218") (pin "2") (pinfunction "2_2") (pintype "passive"))
      (node (ref "U2") (pin "K5") (pinfunction "NCONFIG_K5") (pintype "bidirectional"))
    )
    (net (code "273") (name "/nCSO") (class "Default")
      (node (ref "U2") (pin "E2") (pinfunction "IO_B1___E2/__DIFFIO_L10P/__FLASH_NCE,NCSO_E2") (pintype "bidirectional"))
      (node (ref "U4") (pin "1") (pinfunction "S#_1") (pintype "passive"))
    )
    (net (code "274") (name "/~{RESET}") (class "Default")
      (node (ref "U2") (pin "T1") (pinfunction "CLK3___T1/__DIFFCLK_1N_T1") (pintype "bidirectional"))
    )
    (net (code "275") (name "3V3") (class "Default")
      (node (ref "C171") (pin "2") (pinfunction "2_2") (pintype "passive"))
      (node (ref "C172") (pin "2") (pinfunction "2_2") (pintype "passive"))
      (node (ref "C173") (pin "2") (pinfunction "2_2") (pintype "passive"))
      (node (ref "C174") (pin "2") (pinfunction "2_2") (pintype "passive"))
      (node (ref "C175") (pin "2") (pinfunction "2_2") (pintype "passive"))
      (node (ref "C176") (pin "2") (pinfunction "2_2") (pintype "passive"))
      (node (ref "C177") (pin "2") (pinfunction "2_2") (pintype "passive"))
      (node (ref "C178") (pin "2") (pinfunction "2_2") (pintype "passive"))
      (node (ref "C215") (pin "2") (pinfunction "2_2") (pintype "passive"))
      (node (ref "DIPEX1") (pin "31") (pinfunction "31_31") (pintype "passive"))
      (node (ref "DIPEX2") (pin "27") (pinfunction "27_27") (pintype "passive"))
      (node (ref "R210") (pin "1") (pinfunction "1_1") (pintype "passive"))
      (node (ref "R211") (pin "1") (pinfunction "1_1") (pintype "passive"))
      (node (ref "R212") (pin "1") (pinfunction "1_1") (pintype "passive"))
      (node (ref "R214") (pin "2") (pinfunction "2_2") (pintype "passive"))
      (node (ref "R216") (pin "1") (pinfunction "1_1") (pintype "passive"))
      (node (ref "R218") (pin "1") (pinfunction "1_1") (pintype "passive"))
      (node (ref "R219") (pin "1") (pinfunction "1_1") (pintype "passive"))
      (node (ref "R4DA") (pin "1") (pinfunction "1_1") (pintype "passive"))
      (node (ref "R5DA") (pin "1") (pinfunction "1_1") (pintype "passive"))
      (node (ref "U2") (pin "A2") (pinfunction "VCCIO8_A2") (pintype "power_in"))
      (node (ref "U2") (pin "A21") (pinfunction "VCCIO7_A21") (pintype "power_in"))
      (node (ref "U2") (pin "AA6") (pinfunction "VCCIO3_AA6") (pintype "power_in"))
      (node (ref "U2") (pin "AB2") (pinfunction "VCCIO3_AB2") (pintype "power_in"))
      (node (ref "U2") (pin "AB21") (pinfunction "VCCIO4_AB21") (pintype "power_in"))
      (node (ref "U2") (pin "D11") (pinfunction "VCCIO8_D11") (pintype "power_in"))
      (node (ref "U2") (pin "D12") (pinfunction "VCCIO7_D12") (pintype "power_in"))
      (node (ref "U2") (pin "D14") (pinfunction "VCCIO7_D14") (pintype "power_in"))
      (node (ref "U2") (pin "D16") (pinfunction "VCCIO7_D16") (pintype "power_in"))
      (node (ref "U2") (pin "D18") (pinfunction "VCCIO7_D18") (pintype "power_in"))
      (node (ref "U2") (pin "D4") (pinfunction "VCCIO1_D4") (pintype "power_in"))
      (node (ref "U2") (pin "D5") (pinfunction "VCCIO8_D5") (pintype "power_in"))
      (node (ref "U2") (pin "D9") (pinfunction "VCCIO8_D9") (pintype "power_in"))
      (node (ref "U2") (pin "E19") (pinfunction "VCCIO6_E19") (pintype "power_in"))
      (node (ref "U2") (pin "E8") (pinfunction "VCCIO8_E8") (pintype "power_in"))
      (node (ref "U2") (pin "F4") (pinfunction "VCCIO1_F4") (pintype "power_in"))
      (node (ref "U2") (pin "G19") (pinfunction "VCCIO6_G19") (pintype "power_in"))
      (node (ref "U2") (pin "H4") (pinfunction "VCCIO1_H4") (pintype "power_in"))
      (node (ref "U2") (pin "J20") (pinfunction "VCCIO6_J20") (pintype "power_in"))
      (node (ref "U2") (pin "K4") (pinfunction "VCCIO1_K4") (pintype "power_in"))
      (node (ref "U2") (pin "L18") (pinfunction "MSEL1_L18") (pintype "bidirectional"))
      (node (ref "U2") (pin "L19") (pinfunction "VCCIO6_L19") (pintype "power_in"))
      (node (ref "U2") (pin "N4") (pinfunction "VCCIO2_N4") (pintype "power_in"))
      (node (ref "U2") (pin "P18") (pinfunction "VCCIO5_P18") (pintype "power_in"))
      (node (ref "U2") (pin "R4") (pinfunction "VCCIO2_R4") (pintype "power_in"))
      (node (ref "U2") (pin "T19") (pinfunction "VCCIO5_T19") (pintype "power_in"))
      (node (ref "U2") (pin "U4") (pinfunction "VCCIO2_U4") (pintype "power_in"))
      (node (ref "U2") (pin "V19") (pinfunction "VCCIO5_V19") (pintype "power_in"))
      (node (ref "U2") (pin "W11") (pinfunction "VCCIO3_W11") (pintype "power_in"))
      (node (ref "U2") (pin "W12") (pinfunction "VCCIO4_W12") (pintype "power_in"))
      (node (ref "U2") (pin "W16") (pinfunction "VCCIO4_W16") (pintype "power_in"))
      (node (ref "U2") (pin "W18") (pinfunction "VCCIO4_W18") (pintype "power_in"))
      (node (ref "U2") (pin "W4") (pinfunction "VCCIO2_W4") (pintype "power_in"))
      (node (ref "U2") (pin "W5") (pinfunction "VCCIO3_W5") (pintype "power_in"))
      (node (ref "U2") (pin "W9") (pinfunction "VCCIO3_W9") (pintype "power_in"))
      (node (ref "U2") (pin "Y14") (pinfunction "VCCIO4_Y14") (pintype "power_in"))
      (node (ref "U2") (pin "Y19") (pinfunction "VCCIO5_Y19") (pintype "power_in"))
      (node (ref "U4") (pin "3") (pinfunction "W#_3") (pintype "passive"))
      (node (ref "U4") (pin "7") (pinfunction "HOLD#_7") (pintype "passive"))
      (node (ref "U4") (pin "8") (pinfunction "VCC_8") (pintype "passive"))
    )
    (net (code "276") (name "5V_A") (class "Default")
      (node (ref "B2DA") (pin "1") (pinfunction "1_1") (pintype "passive"))
      (node (ref "C6DA") (pin "1") (pinfunction "1_1") (pintype "passive"))
      (node (ref "DIPEX2") (pin "29") (pinfunction "29_29") (pintype "passive"))
    )
    (net (code "277") (name "AGND") (class "Default")
      (node (ref "AD_AIN") (pin "8") (pinfunction "8_8") (pintype "passive"))
      (node (ref "C10AD") (pin "2") (pinfunction "2_2") (pintype "passive"))
      (node (ref "C11AD") (pin "2") (pinfunction "2_2") (pintype "passive"))
      (node (ref "C12AD") (pin "2") (pinfunction "2_2") (pintype "passive"))
      (node (ref "C12DA") (pin "1") (pinfunction "1_1") (pintype "passive"))
      (node (ref "C13AD") (pin "2") (pinfunction "2_2") (pintype "passive"))
      (node (ref "C14AD") (pin "1") (pinfunction "1_1") (pintype "passive"))
      (node (ref "C15AD") (pin "1") (pinfunction "1_1") (pintype "passive"))
      (node (ref "C16AD") (pin "1") (pinfunction "1_1") (pintype "passive"))
      (node (ref "C17AD") (pin "2") (pinfunction "2_2") (pintype "passive"))
      (node (ref "C18AD") (pin "2") (pinfunction "2_2") (pintype "passive"))
      (node (ref "C3AD") (pin "1") (pinfunction "1_1") (pintype "passive"))
      (node (ref "C4AD") (pin "1") (pinfunction "1_1") (pintype "passive"))
      (node (ref "C5AD") (pin "2") (pinfunction "2_2") (pintype "passive"))
      (node (ref "C6AD") (pin "2") (pinfunction "2_2") (pintype "passive"))
      (node (ref "C6DA") (pin "2") (pinfunction "2_2") (pintype "passive"))
      (node (ref "C7AD") (pin "2") (pinfunction "2_2") (pintype "passive"))
      (node (ref "C7DA") (pin "2") (pinfunction "2_2") (pintype "passive"))
      (node (ref "C8AD") (pin "2") (pinfunction "2_2") (pintype "passive"))
      (node (ref "C8DA") (pin "1") (pinfunction "1_1") (pintype "passive"))
      (node (ref "C9AD") (pin "2") (pinfunction "2_2") (pintype "passive"))
      (node (ref "C9DA") (pin "1") (pinfunction "1_1") (pintype "passive"))
      (node (ref "Ca170") (pin "1") (pinfunction "1_1") (pintype "passive"))
      (node (ref "Ca171") (pin "1") (pinfunction "1_1") (pintype "passive"))
      (node (ref "Ca172") (pin "1") (pinfunction "1_1") (pintype "passive"))
      (node (ref "J2DA") (pin "2") (pinfunction "2_2") (pintype "passive"))
      (node (ref "PT1000_A") (pin "2") (pinfunction "2_2") (pintype "passive"))
      (node (ref "PT1000_A") (pin "4") (pinfunction "4_4") (pintype "passive"))
      (node (ref "PT1000_B") (pin "2") (pinfunction "2_2") (pintype "passive"))
      (node (ref "PT1000_B") (pin "4") (pinfunction "4_4") (pintype "passive"))
      (node (ref "R151AD") (pin "1") (pinfunction "1_1") (pintype "passive"))
      (node (ref "R17AD") (pin "2") (pinfunction "2_2") (pintype "passive"))
      (node (ref "R18AD") (pin "2") (pinfunction "2_2") (pintype "passive"))
      (node (ref "R19AD") (pin "2") (pinfunction "2_2") (pintype "passive"))
      (node (ref "R20AD") (pin "2") (pinfunction "2_2") (pintype "passive"))
      (node (ref "R21AD") (pin "2") (pinfunction "2_2") (pintype "passive"))
      (node (ref "R22AD") (pin "2") (pinfunction "2_2") (pintype "passive"))
      (node (ref "R23AD") (pin "2") (pinfunction "2_2") (pintype "passive"))
      (node (ref "R2AD") (pin "1") (pinfunction "1_1") (pintype "passive"))
      (node (ref "R3AD") (pin "1") (pinfunction "1_1") (pintype "passive"))
      (node (ref "R6DA") (pin "2") (pinfunction "2_2") (pintype "passive"))
      (node (ref "R8DA") (pin "2") (pinfunction "2_2") (pintype "passive"))
      (node (ref "R9AD") (pin "1") (pinfunction "1_1") (pintype "passive"))
      (node (ref "RT11") (pin "2") (pinfunction "2_2") (pintype "passive"))
      (node (ref "RT12") (pin "2") (pinfunction "2_2") (pintype "passive"))
      (node (ref "RT21") (pin "2") (pinfunction "2_2") (pintype "passive"))
      (node (ref "RT22") (pin "2") (pinfunction "2_2") (pintype "passive"))
      (node (ref "U148") (pin "4") (pinfunction "V-_4") (pintype "passive"))
      (node (ref "U1AD") (pin "13") (pinfunction "GND_13") (pintype "passive"))
      (node (ref "U1AD") (pin "14") (pinfunction "GND_14") (pintype "passive"))
      (node (ref "U1AD") (pin "8") (pinfunction "CH7_8") (pintype "passive"))
      (node (ref "U247") (pin "4") (pinfunction "V-_4") (pintype "passive"))
      (node (ref "U252") (pin "1") (pinfunction "ADJ_1") (pintype "passive"))
      (node (ref "U2AD") (pin "1") (pinfunction "GND_F_1") (pintype "passive"))
      (node (ref "U2AD") (pin "2") (pinfunction "GND_S_2") (pintype "passive"))
      (node (ref "U2DA") (pin "10") (pinfunction "A0_10") (pintype "passive"))
      (node (ref "U2DA") (pin "7") (pinfunction "GND_7") (pintype "passive"))
      (node (ref "U3DA") (pin "11") (pinfunction "GND_11") (pintype "power_in"))
    )
    (net (code "278") (name "AVCC") (class "Default")
      (node (ref "C12AD") (pin "1") (pinfunction "1_1") (pintype "passive"))
      (node (ref "C13AD") (pin "1") (pinfunction "1_1") (pintype "passive"))
      (node (ref "C17AD") (pin "1") (pinfunction "1_1") (pintype "passive"))
      (node (ref "C18AD") (pin "1") (pinfunction "1_1") (pintype "passive"))
      (node (ref "C3AD") (pin "2") (pinfunction "2_2") (pintype "passive"))
      (node (ref "C4AD") (pin "2") (pinfunction "2_2") (pintype "passive"))
      (node (ref "Ca170") (pin "2") (pinfunction "2_2") (pintype "passive"))
      (node (ref "R1AD") (pin "1") (pinfunction "1_1") (pintype "passive"))
      (node (ref "U148") (pin "8") (pinfunction "V+_8") (pintype "passive"))
      (node (ref "U1AD") (pin "10") (pinfunction "~{SHDN}_10") (pintype "passive"))
      (node (ref "U1AD") (pin "12") (pinfunction "+VCC_12") (pintype "passive"))
      (node (ref "U1AD") (pin "20") (pinfunction "+VCC_20") (pintype "passive"))
      (node (ref "U247") (pin "8") (pinfunction "V+_8") (pintype "passive"))
      (node (ref "U252") (pin "3") (pinfunction "VIN_3") (pintype "passive"))
      (node (ref "U2AD") (pin "3") (pinfunction "ENABLE_3") (pintype "passive"))
      (node (ref "U2AD") (pin "4") (pinfunction "Vin_4") (pintype "passive"))
    )
    (net (code "279") (name "AVDD") (class "Default")
      (node (ref "Ca171") (pin "2") (pinfunction "2_2") (pintype "passive"))
      (node (ref "Ca172") (pin "2") (pinfunction "2_2") (pintype "passive"))
      (node (ref "R1247") (pin "1") (pinfunction "1_1") (pintype "passive"))
      (node (ref "R1256") (pin "1") (pinfunction "1_1") (pintype "passive"))
      (node (ref "R1257") (pin "1") (pinfunction "1_1") (pintype "passive"))
      (node (ref "R1292") (pin "1") (pinfunction "1_1") (pintype "passive"))
      (node (ref "R2247") (pin "1") (pinfunction "1_1") (pintype "passive"))
      (node (ref "R2256") (pin "1") (pinfunction "1_1") (pintype "passive"))
      (node (ref "R2257") (pin "1") (pinfunction "1_1") (pintype "passive"))
      (node (ref "R2292") (pin "1") (pinfunction "1_1") (pintype "passive"))
      (node (ref "U252") (pin "2") (pinfunction "VOUT_2") (pintype "passive"))
    )
    (net (code "280") (name "Earth") (class "Default")
      (node (ref "J2DA") (pin "3") (pinfunction "3_3") (pintype "passive"))
    )
    (net (code "281") (name "GND") (class "Default")
      (node (ref "C171") (pin "1") (pinfunction "1_1") (pintype "passive"))
      (node (ref "C172") (pin "1") (pinfunction "1_1") (pintype "passive"))
      (node (ref "C173") (pin "1") (pinfunction "1_1") (pintype "passive"))
      (node (ref "C174") (pin "1") (pinfunction "1_1") (pintype "passive"))
      (node (ref "C175") (pin "1") (pinfunction "1_1") (pintype "passive"))
      (node (ref "C176") (pin "1") (pinfunction "1_1") (pintype "passive"))
      (node (ref "C177") (pin "1") (pinfunction "1_1") (pintype "passive"))
      (node (ref "C178") (pin "1") (pinfunction "1_1") (pintype "passive"))
      (node (ref "C179") (pin "1") (pinfunction "1_1") (pintype "passive"))
      (node (ref "C180") (pin "1") (pinfunction "1_1") (pintype "passive"))
      (node (ref "C181") (pin "1") (pinfunction "1_1") (pintype "passive"))
      (node (ref "C182") (pin "1") (pinfunction "1_1") (pintype "passive"))
      (node (ref "C183") (pin "1") (pinfunction "1_1") (pintype "passive"))
      (node (ref "C184") (pin "1") (pinfunction "1_1") (pintype "passive"))
      (node (ref "C185") (pin "1") (pinfunction "1_1") (pintype "passive"))
      (node (ref "C186") (pin "1") (pinfunction "1_1") (pintype "passive"))
      (node (ref "C188") (pin "1") (pinfunction "1_1") (pintype "passive"))
      (node (ref "C189") (pin "1") (pinfunction "1_1") (pintype "passive"))
      (node (ref "C190") (pin "1") (pinfunction "1_1") (pintype "passive"))
      (node (ref "C191") (pin "1") (pinfunction "1_1") (pintype "passive"))
      (node (ref "C192") (pin "1") (pinfunction "1_1") (pintype "passive"))
      (node (ref "C193") (pin "1") (pinfunction "1_1") (pintype "passive"))
      (node (ref "C194") (pin "1") (pinfunction "1_1") (pintype "passive"))
      (node (ref "C195") (pin "1") (pinfunction "1_1") (pintype "passive"))
      (node (ref "C1AD") (pin "1") (pinfunction "1_1") (pintype "passive"))
      (node (ref "C215") (pin "1") (pinfunction "1_1") (pintype "passive"))
      (node (ref "C2AD") (pin "1") (pinfunction "1_1") (pintype "passive"))
      (node (ref "DIPEX1") (pin "30") (pinfunction "30_30") (pintype "passive"))
      (node (ref "DIPEX1") (pin "32") (pinfunction "32_32") (pintype "passive"))
      (node (ref "DIPEX1") (pin "33") (pinfunction "33_33") (pintype "passive"))
      (node (ref "DIPEX2") (pin "28") (pinfunction "28_28") (pintype "passive"))
      (node (ref "J11") (pin "1") (pinfunction "1_1") (pintype "passive"))
      (node (ref "R213") (pin "1") (pinfunction "1_1") (pintype "passive"))
      (node (ref "R217") (pin "1") (pinfunction "1_1") (pintype "passive"))
      (node (ref "R2AD") (pin "2") (pinfunction "2_2") (pintype "passive"))
      (node (ref "R4AD") (pin "2") (pinfunction "2_2") (pintype "passive"))
      (node (ref "R5AD") (pin "2") (pinfunction "2_2") (pintype "passive"))
      (node (ref "R6AD") (pin "2") (pinfunction "2_2") (pintype "passive"))
      (node (ref "U2") (pin "A1") (pinfunction "GND_A1") (pintype "power_in"))
      (node (ref "U2") (pin "A22") (pinfunction "GND_A22") (pintype "power_in"))
      (node (ref "U2") (pin "AA2") (pinfunction "GND_AA2") (pintype "power_in"))
      (node (ref "U2") (pin "AA22") (pinfunction "GND_AA22") (pintype "power_in"))
      (node (ref "U2") (pin "AB1") (pinfunction "GND_AB1") (pintype "power_in"))
      (node (ref "U2") (pin "AB22") (pinfunction "GND_AB22") (pintype "power_in"))
      (node (ref "U2") (pin "AB6") (pinfunction "GND_AB6") (pintype "power_in"))
      (node (ref "U2") (pin "C11") (pinfunction "GND_C11") (pintype "power_in"))
      (node (ref "U2") (pin "C12") (pinfunction "GND_C12") (pintype "power_in"))
      (node (ref "U2") (pin "C14") (pinfunction "GND_C14") (pintype "power_in"))
      (node (ref "U2") (pin "C16") (pinfunction "GND_C16") (pintype "power_in"))
      (node (ref "U2") (pin "C18") (pinfunction "GND_C18") (pintype "power_in"))
      (node (ref "U2") (pin "C5") (pinfunction "GND_C5") (pintype "power_in"))
      (node (ref "U2") (pin "C9") (pinfunction "GND_C9") (pintype "power_in"))
      (node (ref "U2") (pin "D3") (pinfunction "GND_D3") (pintype "power_in"))
      (node (ref "U2") (pin "D8") (pinfunction "GND_D8") (pintype "power_in"))
      (node (ref "U2") (pin "E18") (pinfunction "GNDA2_E18") (pintype "power_in"))
      (node (ref "U2") (pin "E20") (pinfunction "GND_E20") (pintype "power_in"))
      (node (ref "U2") (pin "F12") (pinfunction "GND_F12") (pintype "power_in"))
      (node (ref "U2") (pin "F3") (pinfunction "GND_F3") (pintype "power_in"))
      (node (ref "U2") (pin "F5") (pinfunction "GNDA3_F5") (pintype "power_in"))
      (node (ref "U2") (pin "G2") (pinfunction "GND_G2") (pintype "power_in"))
      (node (ref "U2") (pin "G20") (pinfunction "GND_G20") (pintype "power_in"))
      (node (ref "U2") (pin "H12") (pinfunction "GND_H12") (pintype "power_in"))
      (node (ref "U2") (pin "H13") (pinfunction "GND_H13") (pintype "power_in"))
      (node (ref "U2") (pin "H3") (pinfunction "GND_H3") (pintype "power_in"))
      (node (ref "U2") (pin "J15") (pinfunction "GND_J15") (pintype "power_in"))
      (node (ref "U2") (pin "J19") (pinfunction "GND_J19") (pintype "power_in"))
      (node (ref "U2") (pin "J9") (pinfunction "GND_J9") (pintype "power_in"))
      (node (ref "U2") (pin "K10") (pinfunction "GND_K10") (pintype "power_in"))
      (node (ref "U2") (pin "K11") (pinfunction "GND_K11") (pintype "power_in"))
      (node (ref "U2") (pin "K12") (pinfunction "GND_K12") (pintype "power_in"))
      (node (ref "U2") (pin "K13") (pinfunction "GND_K13") (pintype "power_in"))
      (node (ref "U2") (pin "K16") (pinfunction "GND_K16") (pintype "power_in"))
      (node (ref "U2") (pin "K20") (pinfunction "MSEL3_K20") (pintype "bidirectional"))
      (node (ref "U2") (pin "K3") (pinfunction "GND_K3") (pintype "power_in"))
      (node (ref "U2") (pin "L10") (pinfunction "GND_L10") (pintype "power_in"))
      (node (ref "U2") (pin "L11") (pinfunction "GND_L11") (pintype "power_in"))
      (node (ref "U2") (pin "L12") (pinfunction "GND_L12") (pintype "power_in"))
      (node (ref "U2") (pin "L13") (pinfunction "GND_L13") (pintype "power_in"))
      (node (ref "U2") (pin "L15") (pinfunction "GND_L15") (pintype "power_in"))
      (node (ref "U2") (pin "L17") (pinfunction "MSEL2_L17") (pintype "bidirectional"))
      (node (ref "U2") (pin "L20") (pinfunction "GND_L20") (pintype "power_in"))
      (node (ref "U2") (pin "M10") (pinfunction "GND_M10") (pintype "power_in"))
      (node (ref "U2") (pin "M11") (pinfunction "GND_M11") (pintype "power_in"))
      (node (ref "U2") (pin "M12") (pinfunction "GND_M12") (pintype "power_in"))
      (node (ref "U2") (pin "M13") (pinfunction "GND_M13") (pintype "power_in"))
      (node (ref "U2") (pin "M17") (pinfunction "MSEL0_M17") (pintype "bidirectional"))
      (node (ref "U2") (pin "N10") (pinfunction "GND_N10") (pintype "power_in"))
      (node (ref "U2") (pin "N11") (pinfunction "GND_N11") (pintype "power_in"))
      (node (ref "U2") (pin "N12") (pinfunction "GND_N12") (pintype "power_in"))
      (node (ref "U2") (pin "N13") (pinfunction "GND_N13") (pintype "power_in"))
      (node (ref "U2") (pin "N15") (pinfunction "GND_N15") (pintype "power_in"))
      (node (ref "U2") (pin "N3") (pinfunction "GND_N3") (pintype "power_in"))
      (node (ref "U2") (pin "P19") (pinfunction "GND_P19") (pintype "power_in"))
      (node (ref "U2") (pin "P8") (pinfunction "GND_P8") (pintype "power_in"))
      (node (ref "U2") (pin "R11") (pinfunction "GND_R11") (pintype "power_in"))
      (node (ref "U2") (pin "R13") (pinfunction "GND_R13") (pintype "power_in"))
      (node (ref "U2") (pin "R3") (pinfunction "GND_R3") (pintype "power_in"))
      (node (ref "U2") (pin "R9") (pinfunction "GND_R9") (pintype "power_in"))
      (node (ref "U2") (pin "T20") (pinfunction "GND_T20") (pintype "power_in"))
      (node (ref "U2") (pin "U3") (pinfunction "GND_U3") (pintype "power_in"))
      (node (ref "U2") (pin "U5") (pinfunction "GNDA1_U5") (pintype "power_in"))
      (node (ref "U2") (pin "V18") (pinfunction "GNDA4_V18") (pintype "power_in"))
      (node (ref "U2") (pin "V20") (pinfunction "GND_V20") (pintype "power_in"))
      (node (ref "U2") (pin "W3") (pinfunction "GND_W3") (pintype "power_in"))
      (node (ref "U2") (pin "Y11") (pinfunction "GND_Y11") (pintype "power_in"))
      (node (ref "U2") (pin "Y12") (pinfunction "GND_Y12") (pintype "power_in"))
      (node (ref "U2") (pin "Y15") (pinfunction "GND_Y15") (pintype "power_in"))
      (node (ref "U2") (pin "Y16") (pinfunction "GND_Y16") (pintype "power_in"))
      (node (ref "U2") (pin "Y18") (pinfunction "GND_Y18") (pintype "power_in"))
      (node (ref "U2") (pin "Y20") (pinfunction "GND_Y20") (pintype "power_in"))
      (node (ref "U2") (pin "Y5") (pinfunction "GND_Y5") (pintype "power_in"))
      (node (ref "U2") (pin "Y9") (pinfunction "GND_Y9") (pintype "power_in"))
      (node (ref "U4") (pin "4") (pinfunction "VSS_4") (pintype "passive"))
    )
    (net (code "282") (name "Net-(AD_AIN-Pad1)") (class "Default")
      (node (ref "AD_AIN") (pin "1") (pinfunction "1_1") (pintype "passive"))
      (node (ref "R10AD") (pin "1") (pinfunction "1_1") (pintype "passive"))
    )
    (net (code "283") (name "Net-(AD_AIN-Pad2)") (class "Default")
      (node (ref "AD_AIN") (pin "2") (pinfunction "2_2") (pintype "passive"))
      (node (ref "R11AD") (pin "1") (pinfunction "1_1") (pintype "passive"))
    )
    (net (code "284") (name "Net-(AD_AIN-Pad3)") (class "Default")
      (node (ref "AD_AIN") (pin "3") (pinfunction "3_3") (pintype "passive"))
      (node (ref "R12AD") (pin "1") (pinfunction "1_1") (pintype "passive"))
    )
    (net (code "285") (name "Net-(AD_AIN-Pad4)") (class "Default")
      (node (ref "AD_AIN") (pin "4") (pinfunction "4_4") (pintype "passive"))
      (node (ref "R13AD") (pin "1") (pinfunction "1_1") (pintype "passive"))
    )
    (net (code "286") (name "Net-(AD_AIN-Pad5)") (class "Default")
      (node (ref "AD_AIN") (pin "5") (pinfunction "5_5") (pintype "passive"))
      (node (ref "R14AD") (pin "1") (pinfunction "1_1") (pintype "passive"))
    )
    (net (code "287") (name "Net-(AD_AIN-Pad6)") (class "Default")
      (node (ref "AD_AIN") (pin "6") (pinfunction "6_6") (pintype "passive"))
      (node (ref "R15AD") (pin "1") (pinfunction "1_1") (pintype "passive"))
    )
    (net (code "288") (name "Net-(AD_AIN-Pad7)") (class "Default")
      (node (ref "AD_AIN") (pin "7") (pinfunction "7_7") (pintype "passive"))
      (node (ref "R16AD") (pin "1") (pinfunction "1_1") (pintype "passive"))
    )
    (net (code "289") (name "Net-(C8DA-Pad2)") (class "Default")
      (node (ref "C8DA") (pin "2") (pinfunction "2_2") (pintype "passive"))
      (node (ref "C9DA") (pin "2") (pinfunction "2_2") (pintype "passive"))
      (node (ref "J2DA") (pin "1") (pinfunction "1_1") (pintype "passive"))
      (node (ref "R7DA") (pin "2") (pinfunction "2_2") (pintype "passive"))
      (node (ref "U3DA") (pin "1") (pinfunction "1_1") (pintype "passive"))
    )
    (net (code "290") (name "Net-(LED11-A)") (class "Default")
      (node (ref "LED11") (pin "1") (pinfunction "A_1") (pintype "passive"))
      (node (ref "R210") (pin "2") (pinfunction "2_2") (pintype "passive"))
    )
    (net (code "291") (name "Net-(LED12-A)") (class "Default")
      (node (ref "LED12") (pin "1") (pinfunction "A_1") (pintype "passive"))
      (node (ref "R211") (pin "2") (pinfunction "2_2") (pintype "passive"))
    )
    (net (code "292") (name "Net-(R6DA-Pad1)") (class "Default")
      (node (ref "R6DA") (pin "1") (pinfunction "1_1") (pintype "passive"))
      (node (ref "R7DA") (pin "1") (pinfunction "1_1") (pintype "passive"))
      (node (ref "U3DA") (pin "2") (pinfunction "2_2") (pintype "passive"))
    )
    (net (code "293") (name "Net-(R1248-Pad2)") (class "Default")
      (node (ref "R1248") (pin "2") (pinfunction "2_2") (pintype "passive"))
      (node (ref "R1250") (pin "1") (pinfunction "1_1") (pintype "passive"))
    )
    (net (code "294") (name "Net-(R1249-Pad1)") (class "Default")
      (node (ref "R1249") (pin "1") (pinfunction "1_1") (pintype "passive"))
      (node (ref "R1292") (pin "2") (pinfunction "2_2") (pintype "passive"))
      (node (ref "RT11") (pin "1") (pinfunction "1_1") (pintype "passive"))
    )
    (net (code "295") (name "Net-(R1256-Pad2)") (class "Default")
      (node (ref "R1256") (pin "2") (pinfunction "2_2") (pintype "passive"))
      (node (ref "R1259") (pin "1") (pinfunction "1_1") (pintype "passive"))
      (node (ref "RT12") (pin "1") (pinfunction "1_1") (pintype "passive"))
    )
    (net (code "296") (name "Net-(R1258-Pad2)") (class "Default")
      (node (ref "R1258") (pin "2") (pinfunction "2_2") (pintype "passive"))
      (node (ref "R1260") (pin "1") (pinfunction "1_1") (pintype "passive"))
    )
    (net (code "297") (name "Net-(R2248-Pad2)") (class "Default")
      (node (ref "R2248") (pin "2") (pinfunction "2_2") (pintype "passive"))
      (node (ref "R2250") (pin "1") (pinfunction "1_1") (pintype "passive"))
    )
    (net (code "298") (name "Net-(R2249-Pad1)") (class "Default")
      (node (ref "R2249") (pin "1") (pinfunction "1_1") (pintype "passive"))
      (node (ref "R2292") (pin "2") (pinfunction "2_2") (pintype "passive"))
      (node (ref "RT21") (pin "1") (pinfunction "1_1") (pintype "passive"))
    )
    (net (code "299") (name "Net-(R2256-Pad2)") (class "Default")
      (node (ref "R2256") (pin "2") (pinfunction "2_2") (pintype "passive"))
      (node (ref "R2259") (pin "1") (pinfunction "1_1") (pintype "passive"))
      (node (ref "RT22") (pin "1") (pinfunction "1_1") (pintype "passive"))
    )
    (net (code "300") (name "Net-(R2258-Pad2)") (class "Default")
      (node (ref "R2258") (pin "2") (pinfunction "2_2") (pintype "passive"))
      (node (ref "R2260") (pin "1") (pinfunction "1_1") (pintype "passive"))
    )
    (net (code "301") (name "Net-(U1AD-BUSY)") (class "Default")
      (node (ref "R7AD") (pin "2") (pinfunction "2_2") (pintype "passive"))
      (node (ref "U1AD") (pin "16") (pinfunction "BUSY_16") (pintype "passive"))
    )
    (net (code "302") (name "Net-(U1AD-COM)") (class "Default")
      (node (ref "R3AD") (pin "2") (pinfunction "2_2") (pintype "passive"))
      (node (ref "U1AD") (pin "9") (pinfunction "COM_9") (pintype "passive"))
    )
    (net (code "303") (name "Net-(U1AD-DOUT)") (class "Default")
      (node (ref "R8AD") (pin "2") (pinfunction "2_2") (pintype "passive"))
      (node (ref "U1AD") (pin "15") (pinfunction "DOUT_15") (pintype "passive"))
    )
    (net (code "304") (name "Net-(U2B-IO_B2___V2{slash}__DIFFIO_L38P{slash}__DQ3L)") (class "Default")
      (node (ref "R542") (pin "1") (pinfunction "1_1") (pintype "passive"))
      (node (ref "U2") (pin "V2") (pinfunction "IO_B2___V2/__DIFFIO_L38P/__DQ3L_V2") (pintype "bidirectional"))
    )
    (net (code "305") (name "Net-(U2C-IO_B3___Y3{slash}__DIFFIO_B4P{slash}__DQ3B)") (class "Default")
      (node (ref "T12") (pin "1") (pinfunction "1_1") (pintype "passive"))
      (node (ref "U2") (pin "Y3") (pinfunction "IO_B3___Y3/__DIFFIO_B4P/__DQ3B_Y3") (pintype "bidirectional"))
    )
    (net (code "306") (name "Net-(U2D-IO_B5___AA21{slash}__DIFFIO_R56P{slash}__DM3R{slash}BWS#3R)") (class "Default")
      (node (ref "T2") (pin "1") (pinfunction "1_1") (pintype "passive"))
      (node (ref "U2") (pin "AA21") (pinfunction "IO_B5___AA21/__DIFFIO_R56P/__DM3R/BWS#3R_AA21") (pintype "bidirectional"))
    )
    (net (code "307") (name "Net-(U2DA-VDD)") (class "Default")
      (node (ref "B2DA") (pin "2") (pinfunction "2_2") (pintype "passive"))
      (node (ref "C7DA") (pin "1") (pinfunction "1_1") (pintype "passive"))
      (node (ref "U2DA") (pin "1") (pinfunction "VDD_1") (pintype "passive"))
    )
    (net (code "308") (name "Net-(U2F-CLK6___T21{slash}__DIFFCLK_3P)") (class "Default")
      (node (ref "T1") (pin "1") (pinfunction "1_1") (pintype "passive"))
      (node (ref "U2") (pin "T21") (pinfunction "CLK6___T21/__DIFFCLK_3P_T21") (pintype "bidirectional"))
    )
    (net (code "309") (name "Net-(U2F-VREFB3N3)") (class "Default")
      (node (ref "T13") (pin "1") (pinfunction "1_1") (pintype "passive"))
      (node (ref "U2") (pin "Y4") (pinfunction "VREFB3N3_Y4") (pintype "bidirectional"))
    )
    (net (code "310") (name "Net-(U2G-NSTATUS)") (class "Default")
      (node (ref "R219") (pin "2") (pinfunction "2_2") (pintype "passive"))
      (node (ref "U2") (pin "K6") (pinfunction "NSTATUS_K6") (pintype "bidirectional"))
    )
    (net (code "311") (name "Net-(U4-Q)") (class "Default")
      (node (ref "R215") (pin "2") (pinfunction "2_2") (pintype "passive"))
      (node (ref "U4") (pin "2") (pinfunction "Q_2") (pintype "passive"))
    )
    (net (code "312") (name "Net-(U148-INPUT1+)") (class "Default")
      (node (ref "R1250") (pin "2") (pinfunction "2_2") (pintype "passive"))
      (node (ref "U148") (pin "3") (pinfunction "INPUT1+_3") (pintype "passive"))
    )
    (net (code "313") (name "Net-(U148-INPUT1-)") (class "Default")
      (node (ref "R1249") (pin "2") (pinfunction "2_2") (pintype "passive"))
      (node (ref "R1263") (pin "1") (pinfunction "1_1") (pintype "passive"))
      (node (ref "U148") (pin "2") (pinfunction "INPUT1-_2") (pintype "passive"))
    )
    (net (code "314") (name "Net-(U148-OUTPUT1)") (class "Default")
      (node (ref "R1252") (pin "1") (pinfunction "1_1") (pintype "passive"))
      (node (ref "R1263") (pin "2") (pinfunction "2_2") (pintype "passive"))
      (node (ref "U148") (pin "1") (pinfunction "OUTPUT1_1") (pintype "passive"))
    )
    (net (code "315") (name "Net-(U247-INPUT1+)") (class "Default")
      (node (ref "R2250") (pin "2") (pinfunction "2_2") (pintype "passive"))
      (node (ref "U247") (pin "3") (pinfunction "INPUT1+_3") (pintype "passive"))
    )
    (net (code "316") (name "Net-(U247-INPUT1-)") (class "Default")
      (node (ref "R2249") (pin "2") (pinfunction "2_2") (pintype "passive"))
      (node (ref "R2263") (pin "1") (pinfunction "1_1") (pintype "passive"))
      (node (ref "U247") (pin "2") (pinfunction "INPUT1-_2") (pintype "passive"))
    )
    (net (code "317") (name "Net-(U247-OUTPUT1)") (class "Default")
      (node (ref "R2252") (pin "1") (pinfunction "1_1") (pintype "passive"))
      (node (ref "R2263") (pin "2") (pinfunction "2_2") (pintype "passive"))
      (node (ref "U247") (pin "1") (pinfunction "OUTPUT1_1") (pintype "passive"))
    )
    (net (code "318") (name "VDD_5V_MAIN") (class "Default")
      (node (ref "C1AD") (pin "2") (pinfunction "2_2") (pintype "passive"))
      (node (ref "C2AD") (pin "2") (pinfunction "2_2") (pintype "passive"))
      (node (ref "R1AD") (pin "2") (pinfunction "2_2") (pintype "passive"))
    )
    (net (code "319") (name "VREF") (class "Default")
      (node (ref "C14AD") (pin "2") (pinfunction "2_2") (pintype "passive"))
      (node (ref "C15AD") (pin "2") (pinfunction "2_2") (pintype "passive"))
      (node (ref "C16AD") (pin "2") (pinfunction "2_2") (pintype "passive"))
      (node (ref "U1AD") (pin "11") (pinfunction "VREF_11") (pintype "passive"))
      (node (ref "U2AD") (pin "5") (pinfunction "Vout_s_5") (pintype "passive"))
      (node (ref "U2AD") (pin "6") (pinfunction "Vout_f_6") (pintype "passive"))
    )
    (net (code "320") (name "unconnected-(U2B-IO_B1___H6{slash}__DIFFIO_L9P{slash}__DQ2L-PadH6)") (class "Default")
      (node (ref "U2") (pin "H6") (pinfunction "IO_B1___H6/__DIFFIO_L9P/__DQ2L_H6") (pintype "bidirectional"))
    )
    (net (code "321") (name "unconnected-(U2B-IO_B1___H8{slash}__DIFFIO_L14P-PadH8)") (class "Default")
      (node (ref "U2") (pin "H8") (pinfunction "IO_B1___H8/__DIFFIO_L14P_H8") (pintype "bidirectional"))
    )
    (net (code "322") (name "unconnected-(U2B-IO_B1___J8{slash}__DIFFIO_L14N-PadJ8)") (class "Default")
      (node (ref "U2") (pin "J8") (pinfunction "IO_B1___J8/__DIFFIO_L14N_J8") (pintype "bidirectional"))
    )
    (net (code "323") (name "unconnected-(U2B-IO_B1___L8{slash}__DIFFIO_L20P-PadL8)") (class "Default")
      (node (ref "U2") (pin "L8") (pinfunction "IO_B1___L8/__DIFFIO_L20P_L8") (pintype "bidirectional"))
    )
    (net (code "324") (name "unconnected-(U2B-IO_B2___L7{slash}__DIFFIO_L30N-PadL7)") (class "Default")
      (node (ref "U2") (pin "L7") (pinfunction "IO_B2___L7/__DIFFIO_L30N_L7") (pintype "bidirectional"))
    )
    (net (code "325") (name "unconnected-(U2B-IO_B2___M6{slash}__DIFFIO_L26N{slash}__DQ0L-PadM6)") (class "Default")
      (node (ref "U2") (pin "M6") (pinfunction "IO_B2___M6/__DIFFIO_L26N/__DQ0L_M6") (pintype "bidirectional"))
    )
    (net (code "326") (name "unconnected-(U2B-IO_B2___M7{slash}__DIFFIO_L41N-PadM7)") (class "Default")
      (node (ref "U2") (pin "M7") (pinfunction "IO_B2___M7/__DIFFIO_L41N_M7") (pintype "bidirectional"))
    )
    (net (code "327") (name "unconnected-(U2B-IO_B2___M8{slash}__DIFFIO_L42P-PadM8)") (class "Default")
      (node (ref "U2") (pin "M8") (pinfunction "IO_B2___M8/__DIFFIO_L42P_M8") (pintype "bidirectional"))
    )
    (net (code "328") (name "unconnected-(U2B-IO_B2___N5{slash}__DQ1L-PadN5)") (class "Default")
      (node (ref "U2") (pin "N5") (pinfunction "IO_B2___N5/__DQ1L_N5") (pintype "bidirectional"))
    )
    (net (code "329") (name "unconnected-(U2B-IO_B2___N6{slash}__DIFFIO_L41P{slash}__DQ3L-PadN6)") (class "Default")
      (node (ref "U2") (pin "N6") (pinfunction "IO_B2___N6/__DIFFIO_L41P/__DQ3L_N6") (pintype "bidirectional"))
    )
    (net (code "330") (name "unconnected-(U2B-IO_B2___N7{slash}__DIFFIO_L49P-PadN7)") (class "Default")
      (node (ref "U2") (pin "N7") (pinfunction "IO_B2___N7/__DIFFIO_L49P_N7") (pintype "bidirectional"))
    )
    (net (code "331") (name "unconnected-(U2B-IO_B2___N8{slash}__DIFFIO_L42N-PadN8)") (class "Default")
      (node (ref "U2") (pin "N8") (pinfunction "IO_B2___N8/__DIFFIO_L42N_N8") (pintype "bidirectional"))
    )
    (net (code "332") (name "unconnected-(U2B-IO_B2___P3{slash}__DIFFIO_L34N{slash}__DQ1L-PadP3)") (class "Default")
      (node (ref "U2") (pin "P3") (pinfunction "IO_B2___P3/__DIFFIO_L34N/__DQ1L_P3") (pintype "bidirectional"))
    )
    (net (code "333") (name "unconnected-(U2B-IO_B2___P6{slash}__DIFFIO_L52P-PadP6)") (class "Default")
      (node (ref "U2") (pin "P6") (pinfunction "IO_B2___P6/__DIFFIO_L52P_P6") (pintype "bidirectional"))
    )
    (net (code "334") (name "unconnected-(U2B-IO_B2___P7{slash}__DIFFIO_L49N-PadP7)") (class "Default")
      (node (ref "U2") (pin "P7") (pinfunction "IO_B2___P7/__DIFFIO_L49N_P7") (pintype "bidirectional"))
    )
    (net (code "335") (name "unconnected-(U2B-IO_B2___R7{slash}__DIFFIO_L53P-PadR7)") (class "Default")
      (node (ref "U2") (pin "R7") (pinfunction "IO_B2___R7/__DIFFIO_L53P_R7") (pintype "bidirectional"))
    )
    (net (code "336") (name "unconnected-(U2B-IO_B2___T7{slash}__DIFFIO_L53N-PadT7)") (class "Default")
      (node (ref "U2") (pin "T7") (pinfunction "IO_B2___T7/__DIFFIO_L53N_T7") (pintype "bidirectional"))
    )
    (net (code "337") (name "unconnected-(U2C-IO_B3___T8{slash}__DIFFIO_B11P-PadT8)") (class "Default")
      (node (ref "U2") (pin "T8") (pinfunction "IO_B3___T8/__DIFFIO_B11P_T8") (pintype "bidirectional"))
    )
    (net (code "338") (name "unconnected-(U2C-IO_B3___T9{slash}__DIFFIO_B11N-PadT9)") (class "Default")
      (node (ref "U2") (pin "T9") (pinfunction "IO_B3___T9/__DIFFIO_B11N_T9") (pintype "bidirectional"))
    )
    (net (code "339") (name "unconnected-(U2C-IO_B3___T10{slash}__DIFFIO_B15P-PadT10)") (class "Default")
      (node (ref "U2") (pin "T10") (pinfunction "IO_B3___T10/__DIFFIO_B15P_T10") (pintype "bidirectional"))
    )
    (net (code "340") (name "unconnected-(U2C-IO_B3___T11{slash}__DIFFIO_B15N-PadT11)") (class "Default")
      (node (ref "U2") (pin "T11") (pinfunction "IO_B3___T11/__DIFFIO_B15N_T11") (pintype "bidirectional"))
    )
    (net (code "341") (name "unconnected-(U2C-IO_B3___U8{slash}__DIFFIO_B3N-PadU8)") (class "Default")
      (node (ref "U2") (pin "U8") (pinfunction "IO_B3___U8/__DIFFIO_B3N_U8") (pintype "bidirectional"))
    )
    (net (code "342") (name "unconnected-(U2C-IO_B3___U9{slash}__DIFFIO_B13P{slash}__DQ3B-PadU9)") (class "Default")
      (node (ref "U2") (pin "U9") (pinfunction "IO_B3___U9/__DIFFIO_B13P/__DQ3B_U9") (pintype "bidirectional"))
    )
    (net (code "343") (name "unconnected-(U2C-IO_B3___V7{slash}__DIFFIO_B7N-PadV7)") (class "Default")
      (node (ref "U2") (pin "V7") (pinfunction "IO_B3___V7/__DIFFIO_B7N_V7") (pintype "bidirectional"))
    )
    (net (code "344") (name "unconnected-(U2C-IO_B3___V8{slash}__DIFFIO_B13N{slash}__DQ3B-PadV8)") (class "Default")
      (node (ref "U2") (pin "V8") (pinfunction "IO_B3___V8/__DIFFIO_B13N/__DQ3B_V8") (pintype "bidirectional"))
    )
    (net (code "345") (name "unconnected-(U2C-IO_B3___V10{slash}__DIFFIO_B16P{slash}__DQS3B{slash}CQ3B#,DPCLK2-PadV10)") (class "Default")
      (node (ref "U2") (pin "V10") (pinfunction "IO_B3___V10/__DIFFIO_B16P/__DQS3B/CQ3B#,DPCLK2_V10") (pintype "bidirectional"))
    )
    (net (code "346") (name "unconnected-(U2C-IO_B3___V11{slash}__DIFFIO_B25N{slash}__DQ5B-PadV11)") (class "Default")
      (node (ref "U2") (pin "V11") (pinfunction "IO_B3___V11/__DIFFIO_B25N/__DQ5B_V11") (pintype "bidirectional"))
    )
    (net (code "347") (name "unconnected-(U2C-IO_B3___W7{slash}__DIFFIO_B12P{slash}__DQ3B-PadW7)") (class "Default")
      (node (ref "U2") (pin "W7") (pinfunction "IO_B3___W7/__DIFFIO_B12P/__DQ3B_W7") (pintype "bidirectional"))
    )
    (net (code "348") (name "unconnected-(U2C-IO_B3___W8{slash}__DQ3B-PadW8)") (class "Default")
      (node (ref "U2") (pin "W8") (pinfunction "IO_B3___W8/__DQ3B_W8") (pintype "bidirectional"))
    )
    (net (code "349") (name "unconnected-(U2C-IO_B3___W10{slash}__DIFFIO_B26P{slash}__DQ5B-PadW10)") (class "Default")
      (node (ref "U2") (pin "W10") (pinfunction "IO_B3___W10/__DIFFIO_B26P/__DQ5B_W10") (pintype "bidirectional"))
    )
    (net (code "350") (name "unconnected-(U2C-IO_B3___Y6{slash}__DIFFIO_B6P{slash}__DQS1B{slash}CQ1B#,CDPCLK2-PadY6)") (class "Default")
      (node (ref "U2") (pin "Y6") (pinfunction "IO_B3___Y6/__DIFFIO_B6P/__DQS1B/CQ1B#,CDPCLK2_Y6") (pintype "bidirectional"))
    )
    (net (code "351") (name "unconnected-(U2C-IO_B3___Y7{slash}__DIFFIO_B12N{slash}__DQ3B-PadY7)") (class "Default")
      (node (ref "U2") (pin "Y7") (pinfunction "IO_B3___Y7/__DIFFIO_B12N/__DQ3B_Y7") (pintype "bidirectional"))
    )
    (net (code "352") (name "unconnected-(U2C-IO_B3___Y8{slash}__DQ5B-PadY8)") (class "Default")
      (node (ref "U2") (pin "Y8") (pinfunction "IO_B3___Y8/__DQ5B_Y8") (pintype "bidirectional"))
    )
    (net (code "353") (name "unconnected-(U2C-IO_B3___Y10{slash}__DIFFIO_B26N{slash}__DQ5B-PadY10)") (class "Default")
      (node (ref "U2") (pin "Y10") (pinfunction "IO_B3___Y10/__DIFFIO_B26N/__DQ5B_Y10") (pintype "bidirectional"))
    )
    (net (code "354") (name "unconnected-(U2C-IO_B4___R14{slash}__DIFFIO_B52P-PadR14)") (class "Default")
      (node (ref "U2") (pin "R14") (pinfunction "IO_B4___R14/__DIFFIO_B52P_R14") (pintype "bidirectional"))
    )
    (net (code "355") (name "unconnected-(U2C-IO_B4___T12{slash}__DIFFIO_B36P-PadT12)") (class "Default")
      (node (ref "U2") (pin "T12") (pinfunction "IO_B4___T12/__DIFFIO_B36P_T12") (pintype "bidirectional"))
    )
    (net (code "356") (name "unconnected-(U2C-IO_B4___T13{slash}__DIFFIO_B36N-PadT13)") (class "Default")
      (node (ref "U2") (pin "T13") (pinfunction "IO_B4___T13/__DIFFIO_B36N_T13") (pintype "bidirectional"))
    )
    (net (code "357") (name "unconnected-(U2C-IO_B4___T14{slash}__DIFFIO_B42P-PadT14)") (class "Default")
      (node (ref "U2") (pin "T14") (pinfunction "IO_B4___T14/__DIFFIO_B42P_T14") (pintype "bidirectional"))
    )
    (net (code "358") (name "unconnected-(U2C-IO_B4___T15{slash}__DIFFIO_B42N{slash}__DQ2B-PadT15)") (class "Default")
      (node (ref "U2") (pin "T15") (pinfunction "IO_B4___T15/__DIFFIO_B42N/__DQ2B_T15") (pintype "bidirectional"))
    )
    (net (code "359") (name "unconnected-(U2C-IO_B4___T16{slash}__PLL4_CLKOUTP-PadT16)") (class "Default")
      (node (ref "U2") (pin "T16") (pinfunction "IO_B4___T16/__PLL4_CLKOUTP_T16") (pintype "bidirectional"))
    )
    (net (code "360") (name "unconnected-(U2C-IO_B4___U12{slash}__DIFFIO_B34P{slash}__DQ4B-PadU12)") (class "Default")
      (node (ref "U2") (pin "U12") (pinfunction "IO_B4___U12/__DIFFIO_B34P/__DQ4B_U12") (pintype "bidirectional"))
    )
    (net (code "361") (name "unconnected-(U2C-IO_B4___U15{slash}__DIFFIO_B40P-PadU15)") (class "Default")
      (node (ref "U2") (pin "U15") (pinfunction "IO_B4___U15/__DIFFIO_B40P_U15") (pintype "bidirectional"))
    )
    (net (code "362") (name "unconnected-(U2C-IO_B4___U16{slash}__DIFFIO_B50P-PadU16)") (class "Default")
      (node (ref "U2") (pin "U16") (pinfunction "IO_B4___U16/__DIFFIO_B50P_U16") (pintype "bidirectional"))
    )
    (net (code "363") (name "unconnected-(U2C-IO_B4___V13{slash}__DQS2B{slash}CQ3B,DPCLK5-PadV13)") (class "Default")
      (node (ref "U2") (pin "V13") (pinfunction "IO_B4___V13/__DQS2B/CQ3B,DPCLK5_V13") (pintype "bidirectional"))
    )
    (net (code "364") (name "unconnected-(U2C-IO_B4___V14{slash}__DIFFIO_B39P{slash}__DQ2B-PadV14)") (class "Default")
      (node (ref "U2") (pin "V14") (pinfunction "IO_B4___V14/__DIFFIO_B39P/__DQ2B_V14") (pintype "bidirectional"))
    )
    (net (code "365") (name "unconnected-(U2C-IO_B4___V15{slash}__DIFFIO_B40N{slash}__DQ2B-PadV15)") (class "Default")
      (node (ref "U2") (pin "V15") (pinfunction "IO_B4___V15/__DIFFIO_B40N/__DQ2B_V15") (pintype "bidirectional"))
    )
    (net (code "366") (name "unconnected-(U2C-IO_B4___W13{slash}__DIFFIO_B32P{slash}__DQ4B-PadW13)") (class "Default")
      (node (ref "U2") (pin "W13") (pinfunction "IO_B4___W13/__DIFFIO_B32P/__DQ4B_W13") (pintype "bidirectional"))
    )
    (net (code "367") (name "unconnected-(U2C-IO_B4___W15{slash}__DIFFIO_B41N{slash}__DQ2B-PadW15)") (class "Default")
      (node (ref "U2") (pin "W15") (pinfunction "IO_B4___W15/__DIFFIO_B41N/__DQ2B_W15") (pintype "bidirectional"))
    )
    (net (code "368") (name "unconnected-(U2C-IO_B4___W17{slash}__DIFFIO_B48P{slash}__DQ2B-PadW17)") (class "Default")
      (node (ref "U2") (pin "W17") (pinfunction "IO_B4___W17/__DIFFIO_B48P/__DQ2B_W17") (pintype "bidirectional"))
    )
    (net (code "369") (name "unconnected-(U2C-IO_B4___Y13{slash}__DIFFIO_B32N{slash}__DQS4B{slash}CQ5B,DPCLK4-PadY13)") (class "Default")
      (node (ref "U2") (pin "Y13") (pinfunction "IO_B4___Y13/__DIFFIO_B32N/__DQS4B/CQ5B,DPCLK4_Y13") (pintype "bidirectional"))
    )
    (net (code "370") (name "unconnected-(U2D-IO_B5___N17{slash}__DIFFIO_R33N-PadN17)") (class "Default")
      (node (ref "U2") (pin "N17") (pinfunction "IO_B5___N17/__DIFFIO_R33N_N17") (pintype "bidirectional"))
    )
    (net (code "371") (name "unconnected-(U2D-IO_B5___N18{slash}__DIFFIO_R33P{slash}__DQS1R{slash}CQ1R#,DPCLK6-PadN18)") (class "Default")
      (node (ref "U2") (pin "N18") (pinfunction "IO_B5___N18/__DIFFIO_R33P/__DQS1R/CQ1R#,DPCLK6_N18") (pintype "bidirectional"))
    )
    (net (code "372") (name "unconnected-(U2D-IO_B5___N19{slash}__DIFFIO_R36P-PadN19)") (class "Default")
      (node (ref "U2") (pin "N19") (pinfunction "IO_B5___N19/__DIFFIO_R36P_N19") (pintype "bidirectional"))
    )
    (net (code "373") (name "unconnected-(U2D-IO_B5___P15{slash}__DIFFIO_R46N-PadP15)") (class "Default")
      (node (ref "U2") (pin "P15") (pinfunction "IO_B5___P15/__DIFFIO_R46N_P15") (pintype "bidirectional"))
    )
    (net (code "374") (name "unconnected-(U2D-IO_B5___P17-PadP17)") (class "Default")
      (node (ref "U2") (pin "P17") (pinfunction "IO_B5___P17_P17") (pintype "bidirectional"))
    )
    (net (code "375") (name "unconnected-(U2D-IO_B6___H16{slash}__DIFFIO_R10P-PadH16)") (class "Default")
      (node (ref "U2") (pin "H16") (pinfunction "IO_B6___H16/__DIFFIO_R10P_H16") (pintype "bidirectional"))
    )
    (net (code "376") (name "unconnected-(U2DA-OUTB-Pad3)") (class "Default")
      (node (ref "U2DA") (pin "3") (pinfunction "OUTB_3") (pintype "passive"))
    )
    (net (code "377") (name "unconnected-(U2DA-OUTC-Pad4)") (class "Default")
      (node (ref "U2DA") (pin "4") (pinfunction "OUTC_4") (pintype "passive"))
    )
    (net (code "378") (name "unconnected-(U2DA-OUTD-Pad6)") (class "Default")
      (node (ref "U2DA") (pin "6") (pinfunction "OUTD_6") (pintype "passive"))
    )
    (net (code "379") (name "unconnected-(U2E-IO_B7___E12{slash}__DIFFIO_T28P-PadE12)") (class "Default")
      (node (ref "U2") (pin "E12") (pinfunction "IO_B7___E12/__DIFFIO_T28P_E12") (pintype "bidirectional"))
    )
    (net (code "380") (name "unconnected-(U2E-IO_B7___G13{slash}__DIFFIO_T42N-PadG13)") (class "Default")
      (node (ref "U2") (pin "G13") (pinfunction "IO_B7___G13/__DIFFIO_T42N_G13") (pintype "bidirectional"))
    )
    (net (code "381") (name "unconnected-(U2E-IO_B7___G14{slash}__DIFFIO_T44P-PadG14)") (class "Default")
      (node (ref "U2") (pin "G14") (pinfunction "IO_B7___G14/__DIFFIO_T44P_G14") (pintype "bidirectional"))
    )
    (net (code "382") (name "unconnected-(U2E-IO_B7___G15{slash}__DIFFIO_T49N-PadG15)") (class "Default")
      (node (ref "U2") (pin "G15") (pinfunction "IO_B7___G15/__DIFFIO_T49N_G15") (pintype "bidirectional"))
    )
    (net (code "383") (name "unconnected-(U2E-IO_B7___G16{slash}__DIFFIO_T50P-PadG16)") (class "Default")
      (node (ref "U2") (pin "G16") (pinfunction "IO_B7___G16/__DIFFIO_T50P_G16") (pintype "bidirectional"))
    )
    (net (code "384") (name "unconnected-(U2E-IO_B7___H14{slash}__DIFFIO_T48P-PadH14)") (class "Default")
      (node (ref "U2") (pin "H14") (pinfunction "IO_B7___H14/__DIFFIO_T48P_H14") (pintype "bidirectional"))
    )
    (net (code "385") (name "unconnected-(U2E-IO_B7___H15{slash}__DIFFIO_T48N-PadH15)") (class "Default")
      (node (ref "U2") (pin "H15") (pinfunction "IO_B7___H15/__DIFFIO_T48N_H15") (pintype "bidirectional"))
    )
    (net (code "386") (name "unconnected-(U2E-IO_B8___C3{slash}__DIFFIO_T3N{slash}__DQ3T-PadC3)") (class "Default")
      (node (ref "U2") (pin "C3") (pinfunction "IO_B8___C3/__DIFFIO_T3N/__DQ3T_C3") (pintype "bidirectional"))
    )
    (net (code "387") (name "unconnected-(U2E-IO_B8___D10{slash}__DIFFIO_T26N{slash}__DQ5T-PadD10)") (class "Default")
      (node (ref "U2") (pin "D10") (pinfunction "IO_B8___D10/__DIFFIO_T26N/__DQ5T_D10") (pintype "bidirectional"))
    )
    (net (code "388") (name "unconnected-(U2E-IO_B8___G11{slash}__DIFFIO_T22N-PadG11)") (class "Default")
      (node (ref "U2") (pin "G11") (pinfunction "IO_B8___G11/__DIFFIO_T22N_G11") (pintype "bidirectional"))
    )
    (net (code "389") (name "unconnected-(U2E-IO_B8___H10{slash}__DIFFIO_T14P-PadH10)") (class "Default")
      (node (ref "U2") (pin "H10") (pinfunction "IO_B8___H10/__DIFFIO_T14P_H10") (pintype "bidirectional"))
    )
    (net (code "390") (name "unconnected-(U2E-IO_B8___H11{slash}__DIFFIO_T14N-PadH11)") (class "Default")
      (node (ref "U2") (pin "H11") (pinfunction "IO_B8___H11/__DIFFIO_T14N_H11") (pintype "bidirectional"))
    )
    (net (code "391") (name "unconnected-(U2F-VREFB3N0-PadU11)") (class "Default")
      (node (ref "U2") (pin "U11") (pinfunction "VREFB3N0_U11") (pintype "bidirectional"))
    )
    (net (code "392") (name "unconnected-(U2F-VREFB3N1-PadV9)") (class "Default")
      (node (ref "U2") (pin "V9") (pinfunction "VREFB3N1_V9") (pintype "bidirectional"))
    )
    (net (code "393") (name "unconnected-(U2F-VREFB4N0-PadV16)") (class "Default")
      (node (ref "U2") (pin "V16") (pinfunction "VREFB4N0_V16") (pintype "bidirectional"))
    )
    (net (code "394") (name "unconnected-(U2F-VREFB4N2-PadW14)") (class "Default")
      (node (ref "U2") (pin "W14") (pinfunction "VREFB4N2_W14") (pintype "bidirectional"))
    )
    (net (code "395") (name "unconnected-(U2F-VREFB4N3-PadV12)") (class "Default")
      (node (ref "U2") (pin "V12") (pinfunction "VREFB4N3_V12") (pintype "bidirectional"))
    )
    (net (code "396") (name "unconnected-(U2F-VREFB5N0-PadM16)") (class "Default")
      (node (ref "U2") (pin "M16") (pinfunction "VREFB5N0_M16") (pintype "bidirectional"))
    )
    (net (code "397") (name "unconnected-(U2F-VREFB5N3-PadW19)") (class "Default")
      (node (ref "U2") (pin "W19") (pinfunction "VREFB5N3_W19") (pintype "bidirectional"))
    )
    (net (code "398") (name "unconnected-(U2F-VREFB7N3-PadE13)") (class "Default")
      (node (ref "U2") (pin "E13") (pinfunction "VREFB7N3_E13") (pintype "bidirectional"))
    )
    (net (code "399") (name "unconnected-(U2F-VREFB8N0-PadC10)") (class "Default")
      (node (ref "U2") (pin "C10") (pinfunction "VREFB8N0_C10") (pintype "bidirectional"))
    )
    (net (code "400") (name "unconnected-(U2F-VREFB8N1-PadE9)") (class "Default")
      (node (ref "U2") (pin "E9") (pinfunction "VREFB8N1_E9") (pintype "bidirectional"))
    )
    (net (code "401") (name "unconnected-(U2G-IO_B7___C13{slash}__DIFFIO_T35N{slash}__PADD7-PadC13)") (class "Default")
      (node (ref "U2") (pin "C13") (pinfunction "IO_B7___C13/__DIFFIO_T35N/__PADD7_C13") (pintype "bidirectional"))
    )
    (net (code "402") (name "unconnected-(U2G-IO_B7___D13{slash}__DIFFIO_T35P{slash}__PADD8{slash}__DQ4T-PadD13)") (class "Default")
      (node (ref "U2") (pin "D13") (pinfunction "IO_B7___D13/__DIFFIO_T35P/__PADD8/__DQ4T_D13") (pintype "bidirectional"))
    )
    (net (code "403") (name "unconnected-(U2G-IO_B7___E11{slash}__DIFFIO_T27N{slash}__PADD13-PadE11)") (class "Default")
      (node (ref "U2") (pin "E11") (pinfunction "IO_B7___E11/__DIFFIO_T27N/__PADD13_E11") (pintype "bidirectional"))
    )
    (net (code "404") (name "unconnected-(U2G-IO_B8___A3{slash}__DIFFIO_T4N{slash}__DATA10{slash}__DQ3T-PadA3)") (class "Default")
      (node (ref "U2") (pin "A3") (pinfunction "IO_B8___A3/__DIFFIO_T4N/__DATA10/__DQ3T_A3") (pintype "bidirectional"))
    )
    (net (code "405") (name "unconnected-(U2G-IO_B8___B7{slash}__DIFFIO_T19P{slash}__DATA4{slash}__DQ5T-PadB7)") (class "Default")
      (node (ref "U2") (pin "B7") (pinfunction "IO_B8___B7/__DIFFIO_T19P/__DATA4/__DQ5T_B7") (pintype "bidirectional"))
    )
    (net (code "406") (name "unconnected-(U2G-IO_B8___C4{slash}__DIFFIO_T3P{slash}__DATA12{slash}__DQS1T{slash}CQ1T#,CDPCLK7-PadC4)") (class "Default")
      (node (ref "U2") (pin "C4") (pinfunction "IO_B8___C4/__DIFFIO_T3P/__DATA12/__DQS1T/CQ1T#,CDPCLK7_C4") (pintype "bidirectional"))
    )
    (net (code "407") (name "unconnected-(U2G-IO_B8___F8{slash}__DIFFIO_T5N{slash}__DATA9{slash}__DQ3T-PadF8)") (class "Default")
      (node (ref "U2") (pin "F8") (pinfunction "IO_B8___F8/__DIFFIO_T5N/__DATA9/__DQ3T_F8") (pintype "bidirectional"))
    )
  )
)
